# axiom_beta_sensor_cmv12000_v0_14_tht_73a.net
KiCad netlist of a schematic drawn in EAGLE
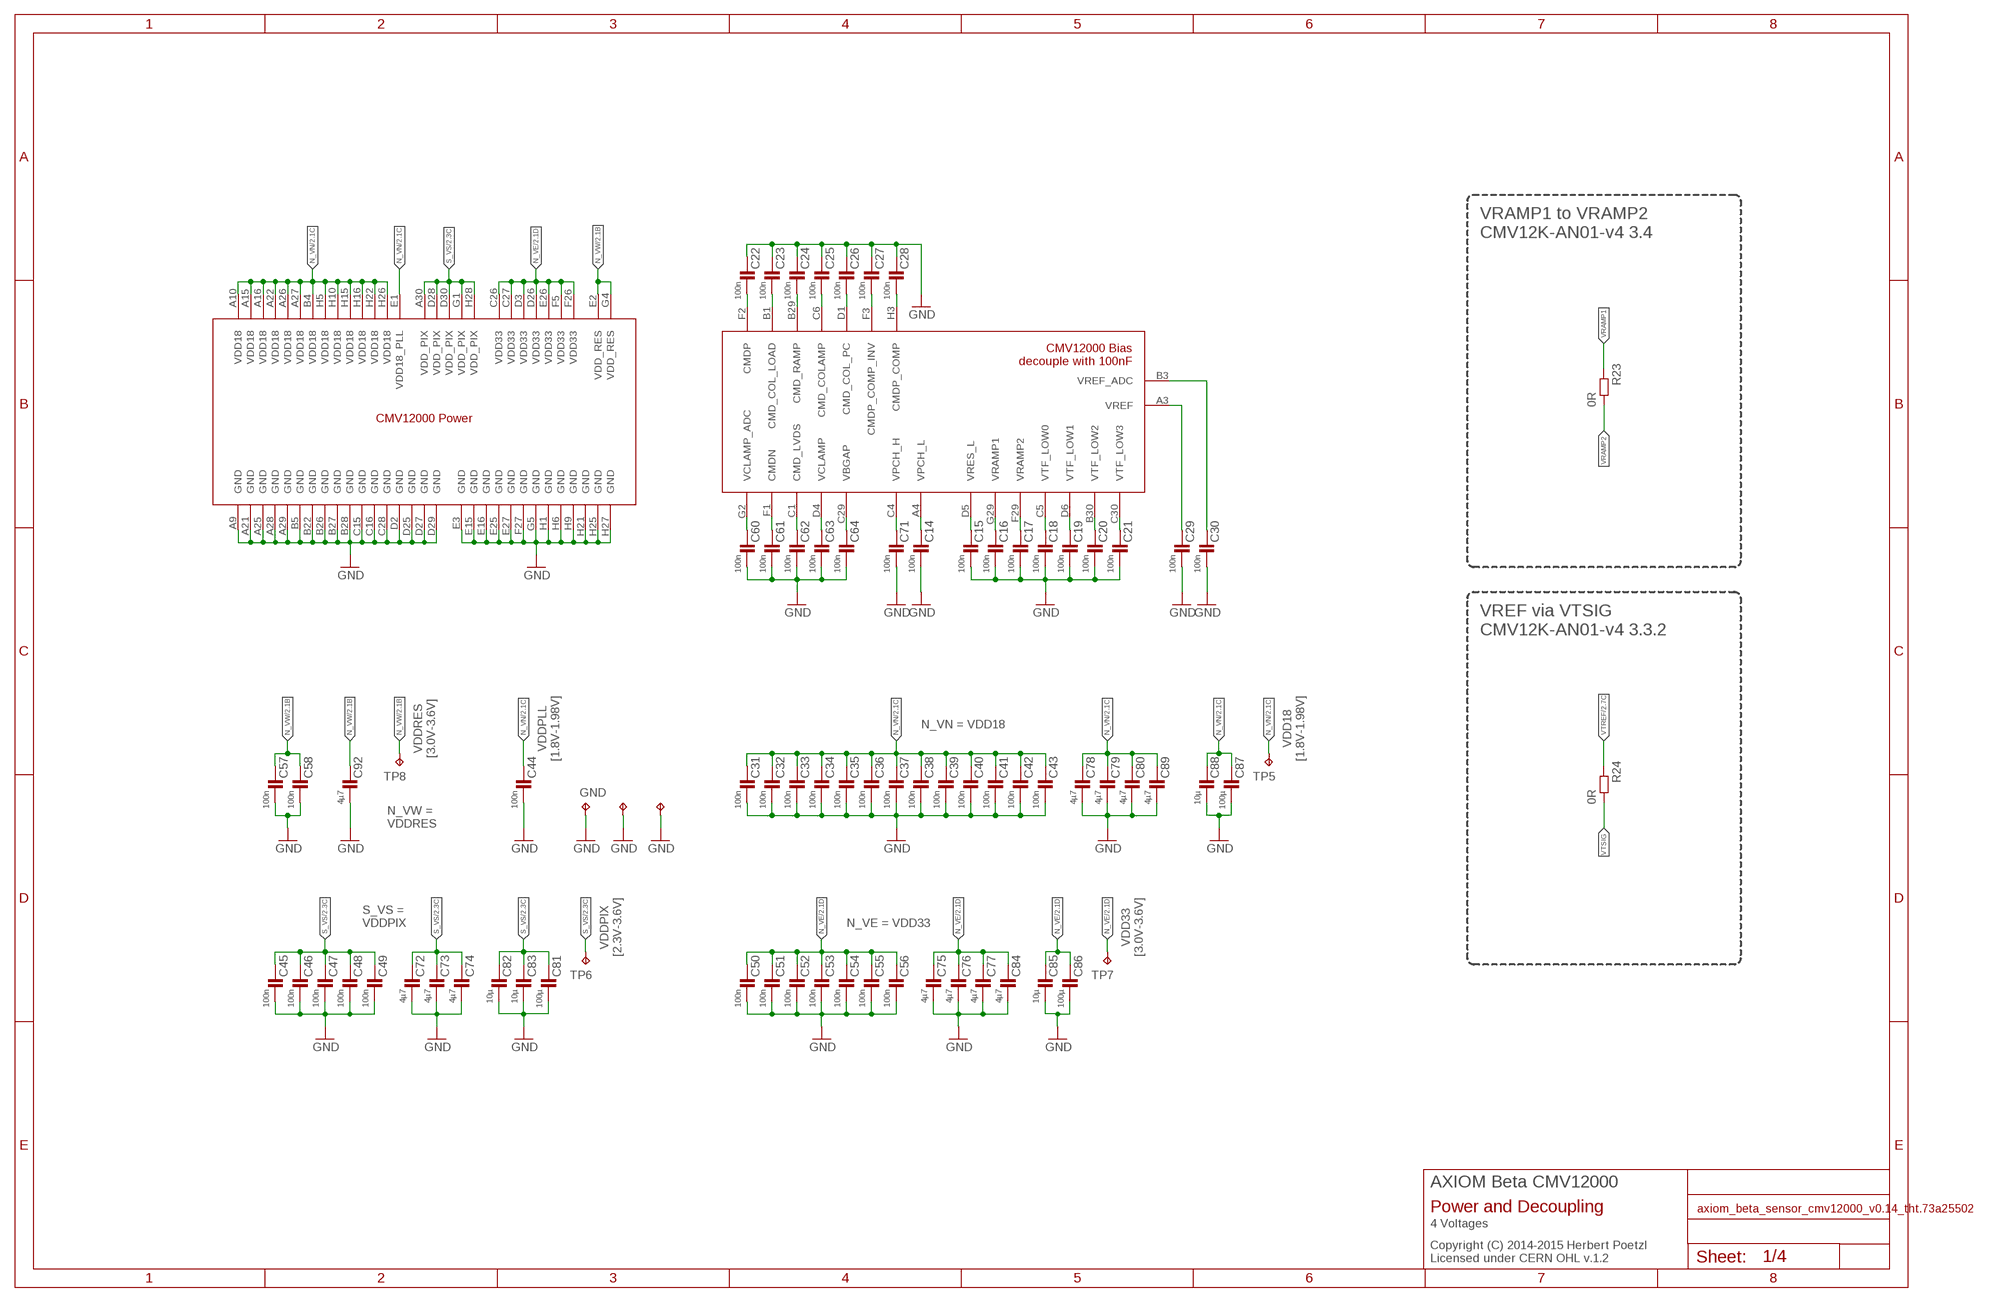
[diagram p0: schematic, sheet 1]
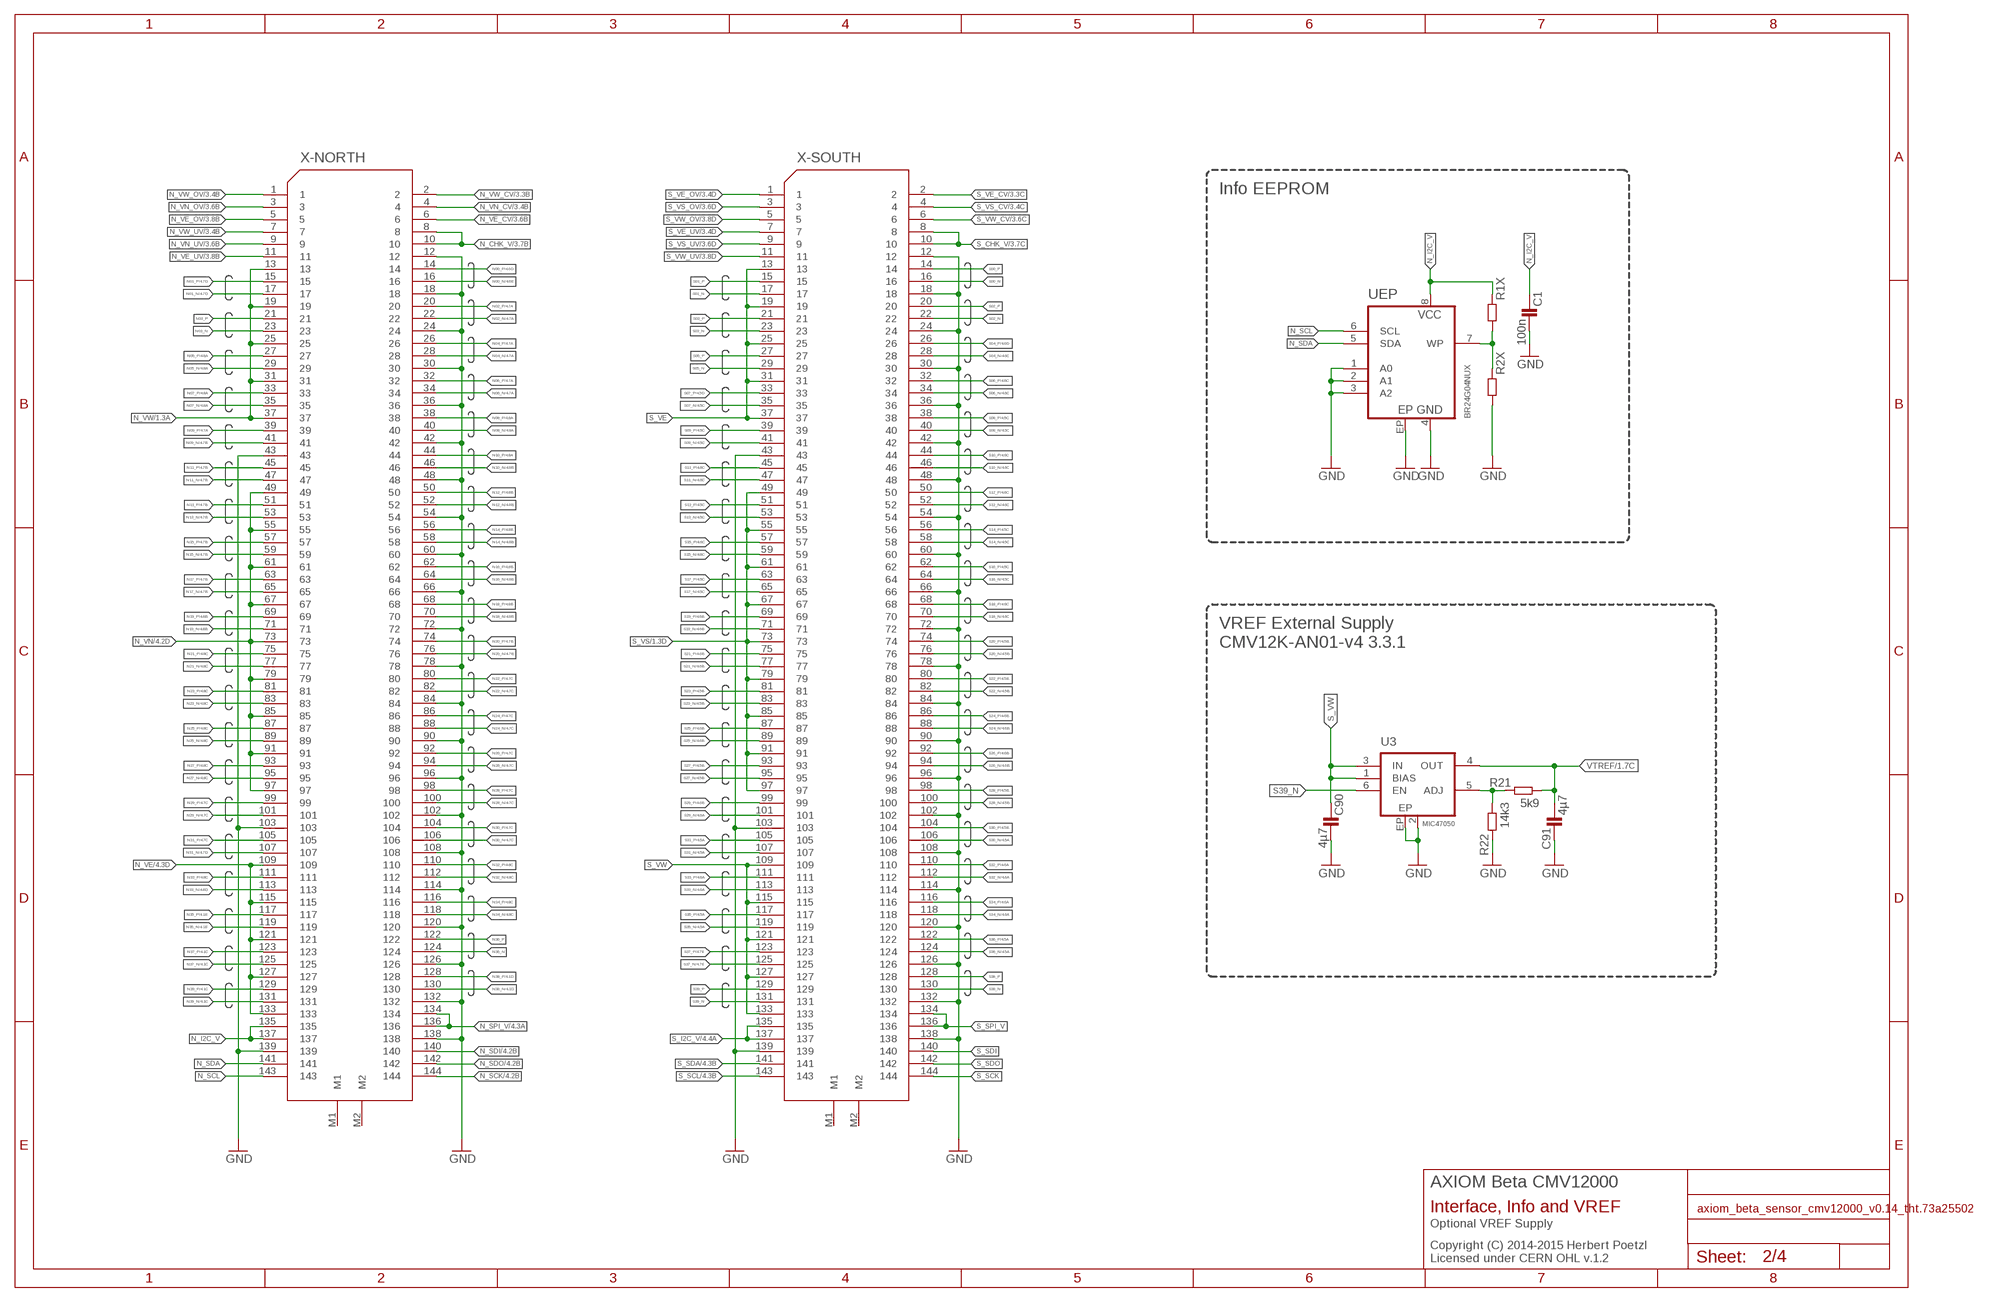
[diagram p1: schematic, sheet 2]
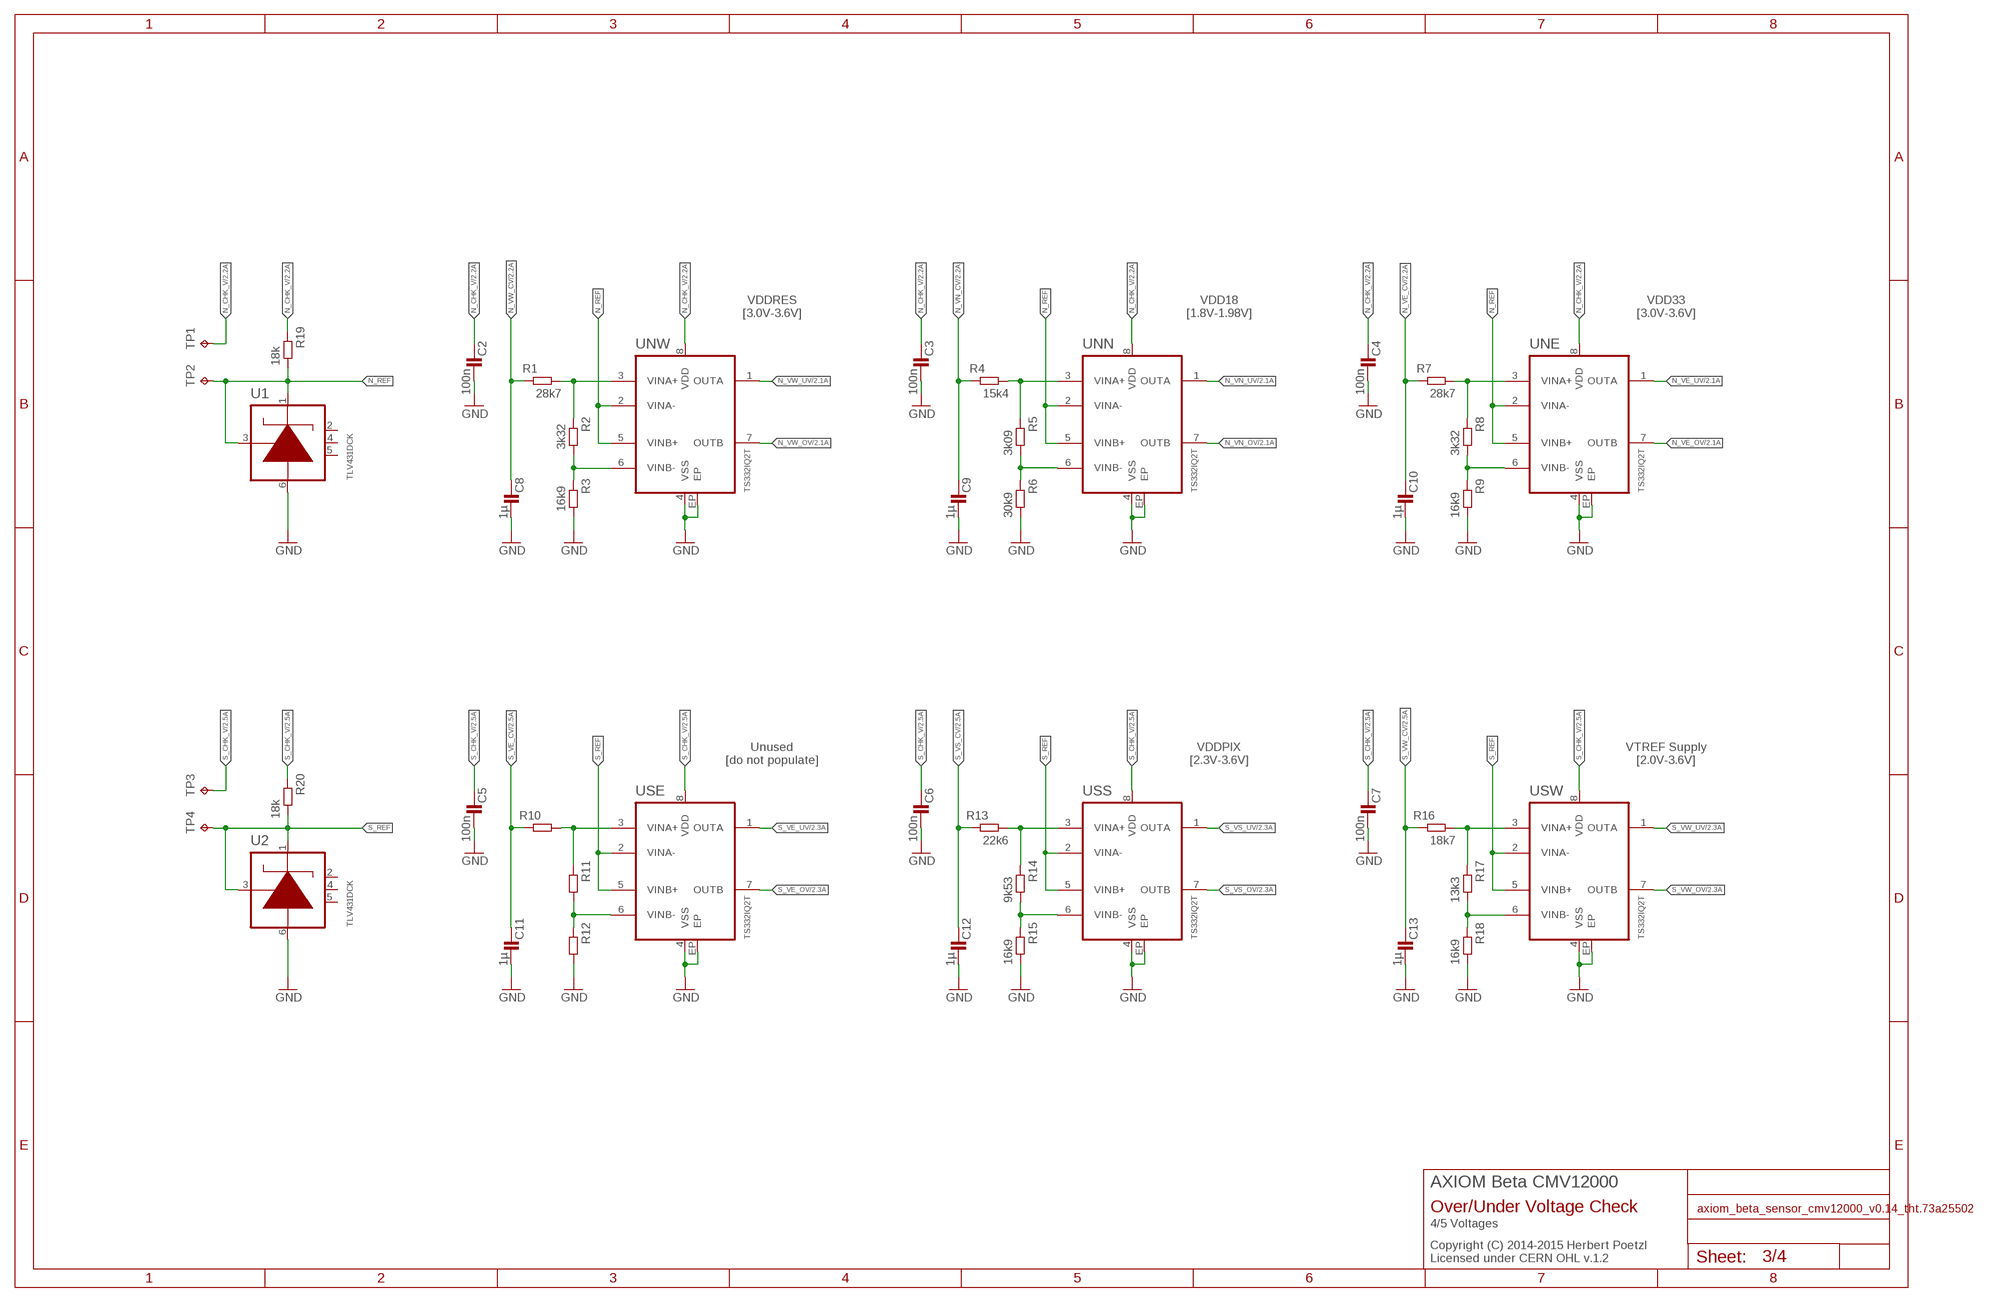
[diagram p2: schematic, sheet 3]
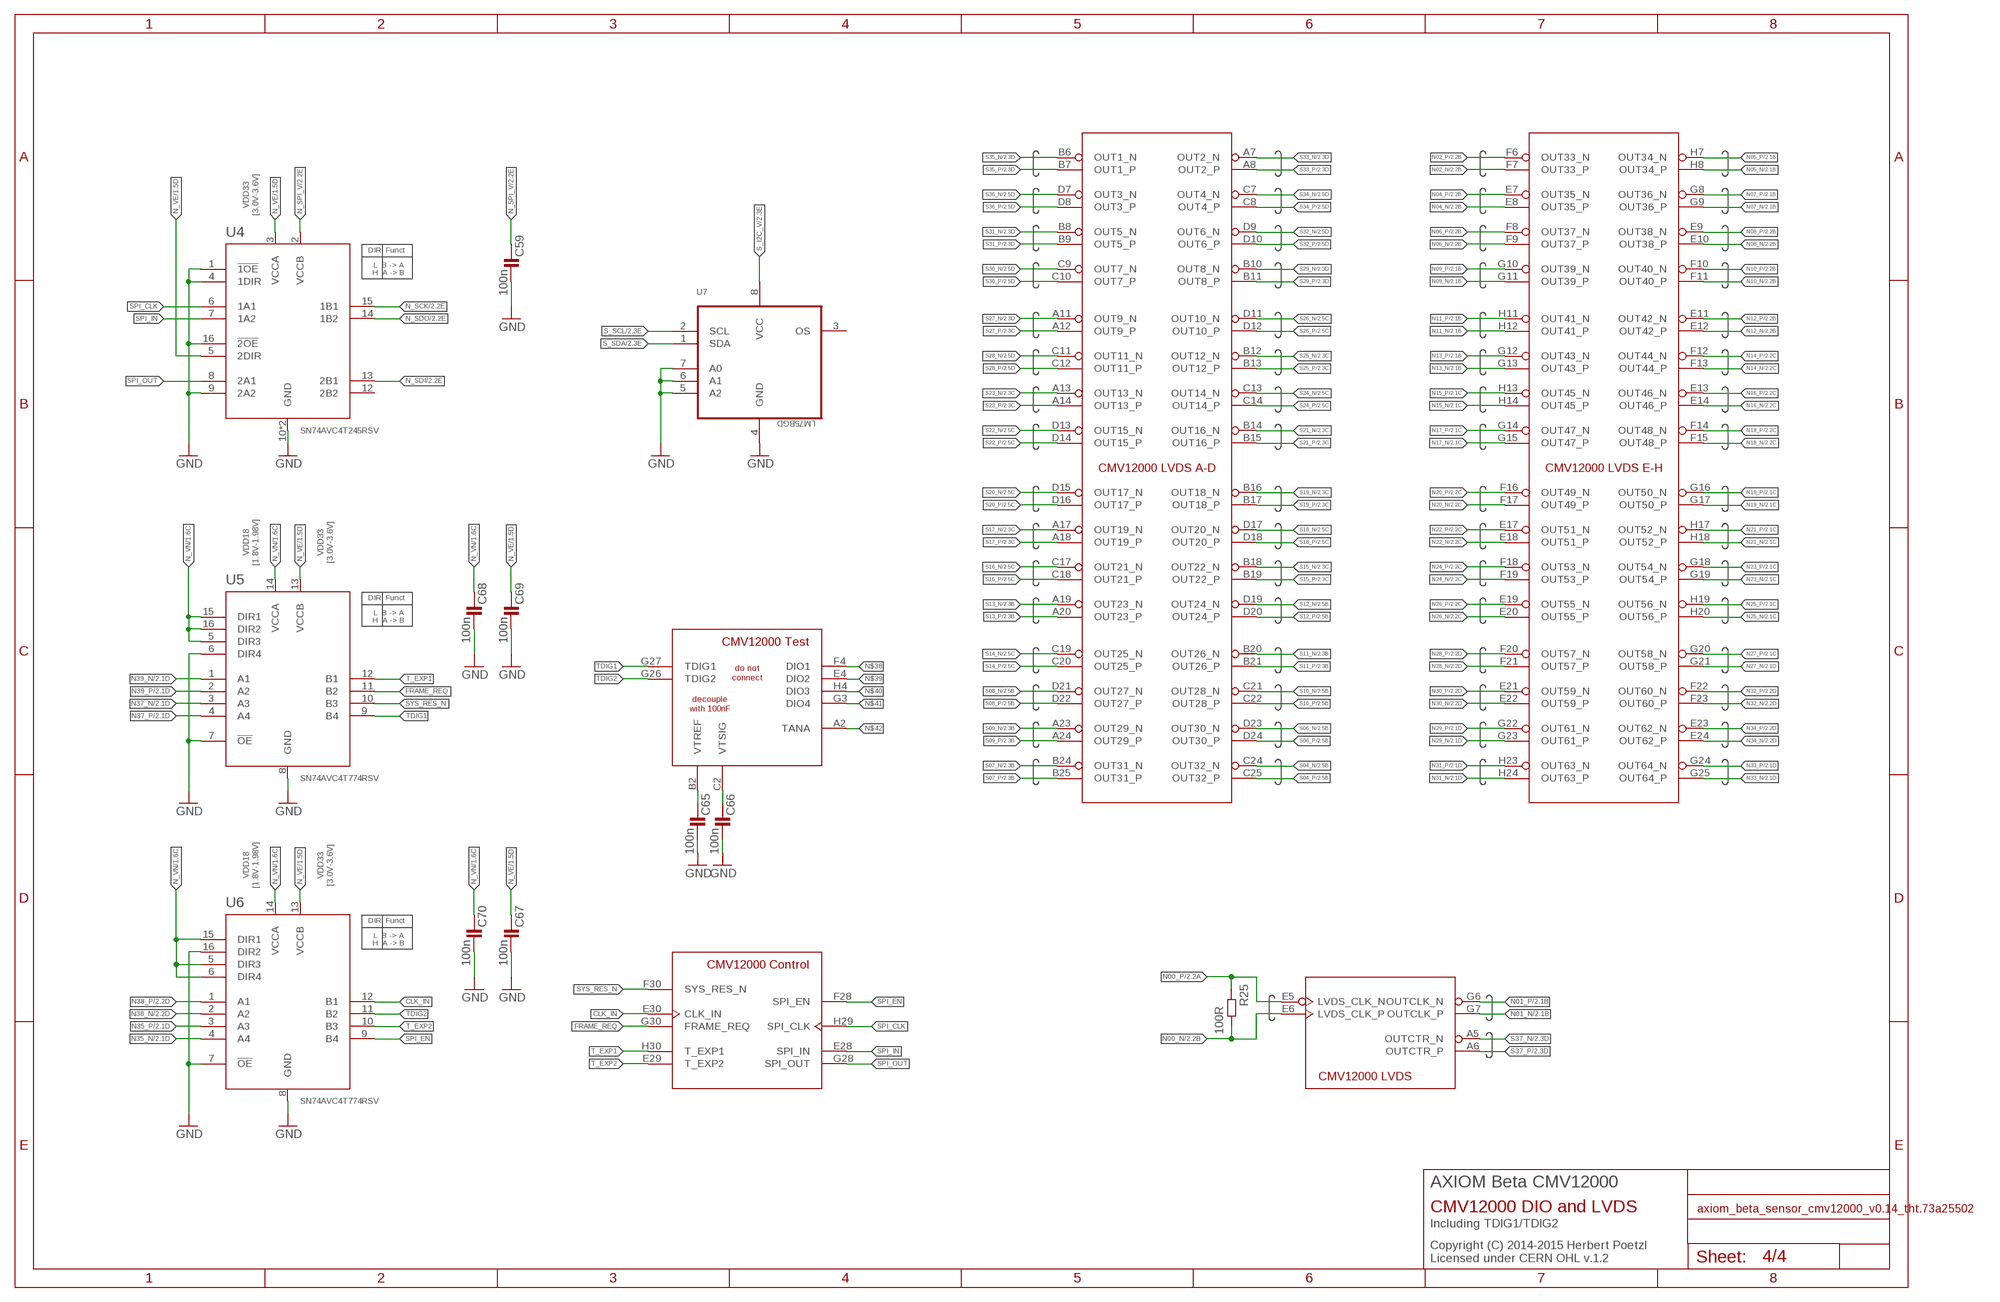
[diagram p3: schematic, sheet 4]

(export (version "E")
  (design (tool "Eeschema 10.0.6"))
  (components
    (comp (ref "C1")
      (value "100n")
      (footprint "eagle-import:0402-C")
      (libsource (lib "eagle-import") (part "C0402-C"))
    )
    (comp (ref "C90")
      (value "4µ7")
      (footprint "eagle-import:0402-C")
      (libsource (lib "eagle-import") (part "C0402-C"))
    )
    (comp (ref "C91")
      (value "4µ7")
      (footprint "eagle-import:0402-C")
      (libsource (lib "eagle-import") (part "C0402-C"))
    )
    (comp (ref "R1X")
      (value "R0402-C")
      (footprint "eagle-import:0402-C")
      (libsource (lib "eagle-import") (part "R0402-C"))
    )
    (comp (ref "R2X")
      (value "R0402-C")
      (footprint "eagle-import:0402-C")
      (libsource (lib "eagle-import") (part "R0402-C"))
    )
    (comp (ref "R21")
      (value "5k9")
      (footprint "eagle-import:0402-C")
      (libsource (lib "eagle-import") (part "R0402-C"))
    )
    (comp (ref "R22")
      (value "14k3")
      (footprint "eagle-import:0402-C")
      (libsource (lib "eagle-import") (part "R0402-C"))
    )
    (comp (ref "U3")
      (value "MIC47050")
      (footprint "eagle-import:MLF-6")
      (libsource (lib "eagle-import") (part "MIC47050-ADJ"))
    )
    (comp (ref "UEP")
      (value "BR24G04NUX")
      (footprint "eagle-import:DFN200X300X100-9N")
      (libsource (lib "eagle-import") (part "BR24G04NUX"))
    )
    (comp (ref "X-NORTH")
      (value "FX10-144P")
      (footprint "eagle-import:FX10A-144P")
      (libsource (lib "eagle-import") (part "FX10-144P"))
    )
    (comp (ref "X-SOUTH")
      (value "FX10-144P")
      (footprint "eagle-import:FX10A-144P")
      (libsource (lib "eagle-import") (part "FX10-144P"))
    )
    (comp (ref "C2")
      (value "100n")
      (footprint "eagle-import:0402-C")
      (libsource (lib "eagle-import") (part "C0402-C"))
    )
    (comp (ref "C3")
      (value "100n")
      (footprint "eagle-import:0402-C")
      (libsource (lib "eagle-import") (part "C0402-C"))
    )
    (comp (ref "C4")
      (value "100n")
      (footprint "eagle-import:0402-C")
      (libsource (lib "eagle-import") (part "C0402-C"))
    )
    (comp (ref "C5")
      (value "100n")
      (footprint "eagle-import:0402-C")
      (libsource (lib "eagle-import") (part "C0402-C"))
    )
    (comp (ref "C6")
      (value "100n")
      (footprint "eagle-import:0402-C")
      (libsource (lib "eagle-import") (part "C0402-C"))
    )
    (comp (ref "C7")
      (value "100n")
      (footprint "eagle-import:0402-C")
      (libsource (lib "eagle-import") (part "C0402-C"))
    )
    (comp (ref "C8")
      (value "1µ")
      (footprint "eagle-import:0402-C")
      (libsource (lib "eagle-import") (part "C0402-C"))
    )
    (comp (ref "C9")
      (value "1µ")
      (footprint "eagle-import:0402-C")
      (libsource (lib "eagle-import") (part "C0402-C"))
    )
    (comp (ref "C10")
      (value "1µ")
      (footprint "eagle-import:0402-C")
      (libsource (lib "eagle-import") (part "C0402-C"))
    )
    (comp (ref "C11")
      (value "1µ")
      (footprint "eagle-import:0402-C")
      (libsource (lib "eagle-import") (part "C0402-C"))
    )
    (comp (ref "C12")
      (value "1µ")
      (footprint "eagle-import:0402-C")
      (libsource (lib "eagle-import") (part "C0402-C"))
    )
    (comp (ref "C13")
      (value "1µ")
      (footprint "eagle-import:0402-C")
      (libsource (lib "eagle-import") (part "C0402-C"))
    )
    (comp (ref "R1")
      (value "28k7")
      (footprint "eagle-import:0402-C")
      (libsource (lib "eagle-import") (part "R0402-C"))
    )
    (comp (ref "R2")
      (value "3k32")
      (footprint "eagle-import:0402-C")
      (libsource (lib "eagle-import") (part "R0402-C"))
    )
    (comp (ref "R3")
      (value "16k9")
      (footprint "eagle-import:0402-C")
      (libsource (lib "eagle-import") (part "R0402-C"))
    )
    (comp (ref "R4")
      (value "15k4")
      (footprint "eagle-import:0402-C")
      (libsource (lib "eagle-import") (part "R0402-C"))
    )
    (comp (ref "R5")
      (value "3k09")
      (footprint "eagle-import:0402-C")
      (libsource (lib "eagle-import") (part "R0402-C"))
    )
    (comp (ref "R6")
      (value "30k9")
      (footprint "eagle-import:0402-C")
      (libsource (lib "eagle-import") (part "R0402-C"))
    )
    (comp (ref "R7")
      (value "28k7")
      (footprint "eagle-import:0402-C")
      (libsource (lib "eagle-import") (part "R0402-C"))
    )
    (comp (ref "R8")
      (value "3k32")
      (footprint "eagle-import:0402-C")
      (libsource (lib "eagle-import") (part "R0402-C"))
    )
    (comp (ref "R9")
      (value "16k9")
      (footprint "eagle-import:0402-C")
      (libsource (lib "eagle-import") (part "R0402-C"))
    )
    (comp (ref "R10")
      (value "R0402-C")
      (footprint "eagle-import:0402-C")
      (libsource (lib "eagle-import") (part "R0402-C"))
    )
    (comp (ref "R11")
      (value "R0402-C")
      (footprint "eagle-import:0402-C")
      (libsource (lib "eagle-import") (part "R0402-C"))
    )
    (comp (ref "R12")
      (value "R0402-C")
      (footprint "eagle-import:0402-C")
      (libsource (lib "eagle-import") (part "R0402-C"))
    )
    (comp (ref "R13")
      (value "22k6")
      (footprint "eagle-import:0402-C")
      (libsource (lib "eagle-import") (part "R0402-C"))
    )
    (comp (ref "R14")
      (value "9k53")
      (footprint "eagle-import:0402-C")
      (libsource (lib "eagle-import") (part "R0402-C"))
    )
    (comp (ref "R15")
      (value "16k9")
      (footprint "eagle-import:0402-C")
      (libsource (lib "eagle-import") (part "R0402-C"))
    )
    (comp (ref "R16")
      (value "18k7")
      (footprint "eagle-import:0402-C")
      (libsource (lib "eagle-import") (part "R0402-C"))
    )
    (comp (ref "R17")
      (value "13k3")
      (footprint "eagle-import:0402-C")
      (libsource (lib "eagle-import") (part "R0402-C"))
    )
    (comp (ref "R18")
      (value "16k9")
      (footprint "eagle-import:0402-C")
      (libsource (lib "eagle-import") (part "R0402-C"))
    )
    (comp (ref "R19")
      (value "18k")
      (footprint "eagle-import:0402-C")
      (libsource (lib "eagle-import") (part "R0402-C"))
    )
    (comp (ref "R20")
      (value "18k")
      (footprint "eagle-import:0402-C")
      (libsource (lib "eagle-import") (part "R0402-C"))
    )
    (comp (ref "TP1")
      (value "TPTP10R")
      (footprint "eagle-import:TP10R")
      (libsource (lib "eagle-import") (part "TPTP10R"))
    )
    (comp (ref "TP2")
      (value "TPTP10R")
      (footprint "eagle-import:TP10R")
      (libsource (lib "eagle-import") (part "TPTP10R"))
    )
    (comp (ref "TP3")
      (value "TPTP10R")
      (footprint "eagle-import:TP10R")
      (libsource (lib "eagle-import") (part "TPTP10R"))
    )
    (comp (ref "TP4")
      (value "TPTP10R")
      (footprint "eagle-import:TP10R")
      (libsource (lib "eagle-import") (part "TPTP10R"))
    )
    (comp (ref "U1")
      (value "TLV431DCK")
      (footprint "eagle-import:SOT65P210X110-6N")
      (libsource (lib "eagle-import") (part "TLV431DCK"))
    )
    (comp (ref "U2")
      (value "TLV431DCK")
      (footprint "eagle-import:SOT65P210X110-6N")
      (libsource (lib "eagle-import") (part "TLV431DCK"))
    )
    (comp (ref "UNE")
      (value "TS332IQ2T")
      (footprint "eagle-import:DFN200X200X100-9N")
      (libsource (lib "eagle-import") (part "TS332IQ2T"))
    )
    (comp (ref "UNN")
      (value "TS332IQ2T")
      (footprint "eagle-import:DFN200X200X100-9N")
      (libsource (lib "eagle-import") (part "TS332IQ2T"))
    )
    (comp (ref "UNW")
      (value "TS332IQ2T")
      (footprint "eagle-import:DFN200X200X100-9N")
      (libsource (lib "eagle-import") (part "TS332IQ2T"))
    )
    (comp (ref "USE")
      (value "TS332IQ2T")
      (footprint "eagle-import:DFN200X200X100-9N")
      (libsource (lib "eagle-import") (part "TS332IQ2T"))
    )
    (comp (ref "USS")
      (value "TS332IQ2T")
      (footprint "eagle-import:DFN200X200X100-9N")
      (libsource (lib "eagle-import") (part "TS332IQ2T"))
    )
    (comp (ref "USW")
      (value "TS332IQ2T")
      (footprint "eagle-import:DFN200X200X100-9N")
      (libsource (lib "eagle-import") (part "TS332IQ2T"))
    )
    (comp (ref "C14")
      (value "100n")
      (footprint "eagle-import:0402-C")
      (libsource (lib "eagle-import") (part "C0402-C"))
    )
    (comp (ref "C15")
      (value "100n")
      (footprint "eagle-import:0402-C")
      (libsource (lib "eagle-import") (part "C0402-C"))
    )
    (comp (ref "C16")
      (value "100n")
      (footprint "eagle-import:0402-C")
      (libsource (lib "eagle-import") (part "C0402-C"))
    )
    (comp (ref "C17")
      (value "100n")
      (footprint "eagle-import:0402-C")
      (libsource (lib "eagle-import") (part "C0402-C"))
    )
    (comp (ref "C18")
      (value "100n")
      (footprint "eagle-import:0402-C")
      (libsource (lib "eagle-import") (part "C0402-C"))
    )
    (comp (ref "C19")
      (value "100n")
      (footprint "eagle-import:0402-C")
      (libsource (lib "eagle-import") (part "C0402-C"))
    )
    (comp (ref "C20")
      (value "100n")
      (footprint "eagle-import:0402-C")
      (libsource (lib "eagle-import") (part "C0402-C"))
    )
    (comp (ref "C21")
      (value "100n")
      (footprint "eagle-import:0402-C")
      (libsource (lib "eagle-import") (part "C0402-C"))
    )
    (comp (ref "C22")
      (value "100n")
      (footprint "eagle-import:0402-C")
      (libsource (lib "eagle-import") (part "C0402-C"))
    )
    (comp (ref "C23")
      (value "100n")
      (footprint "eagle-import:0402-C")
      (libsource (lib "eagle-import") (part "C0402-C"))
    )
    (comp (ref "C24")
      (value "100n")
      (footprint "eagle-import:0402-C")
      (libsource (lib "eagle-import") (part "C0402-C"))
    )
    (comp (ref "C25")
      (value "100n")
      (footprint "eagle-import:0402-C")
      (libsource (lib "eagle-import") (part "C0402-C"))
    )
    (comp (ref "C26")
      (value "100n")
      (footprint "eagle-import:0402-C")
      (libsource (lib "eagle-import") (part "C0402-C"))
    )
    (comp (ref "C27")
      (value "100n")
      (footprint "eagle-import:0402-C")
      (libsource (lib "eagle-import") (part "C0402-C"))
    )
    (comp (ref "C28")
      (value "100n")
      (footprint "eagle-import:0402-C")
      (libsource (lib "eagle-import") (part "C0402-C"))
    )
    (comp (ref "C29")
      (value "100n")
      (footprint "eagle-import:0402-C")
      (libsource (lib "eagle-import") (part "C0402-C"))
    )
    (comp (ref "C30")
      (value "100n")
      (footprint "eagle-import:0402-C")
      (libsource (lib "eagle-import") (part "C0402-C"))
    )
    (comp (ref "C31")
      (value "100n")
      (footprint "eagle-import:0402-C")
      (libsource (lib "eagle-import") (part "C0402-C"))
    )
    (comp (ref "C32")
      (value "100n")
      (footprint "eagle-import:0402-C")
      (libsource (lib "eagle-import") (part "C0402-C"))
    )
    (comp (ref "C33")
      (value "100n")
      (footprint "eagle-import:0402-C")
      (libsource (lib "eagle-import") (part "C0402-C"))
    )
    (comp (ref "C34")
      (value "100n")
      (footprint "eagle-import:0402-C")
      (libsource (lib "eagle-import") (part "C0402-C"))
    )
    (comp (ref "C35")
      (value "100n")
      (footprint "eagle-import:0402-C")
      (libsource (lib "eagle-import") (part "C0402-C"))
    )
    (comp (ref "C36")
      (value "100n")
      (footprint "eagle-import:0402-C")
      (libsource (lib "eagle-import") (part "C0402-C"))
    )
    (comp (ref "C37")
      (value "100n")
      (footprint "eagle-import:0402-C")
      (libsource (lib "eagle-import") (part "C0402-C"))
    )
    (comp (ref "C38")
      (value "100n")
      (footprint "eagle-import:0402-C")
      (libsource (lib "eagle-import") (part "C0402-C"))
    )
    (comp (ref "C39")
      (value "100n")
      (footprint "eagle-import:0402-C")
      (libsource (lib "eagle-import") (part "C0402-C"))
    )
    (comp (ref "C40")
      (value "100n")
      (footprint "eagle-import:0402-C")
      (libsource (lib "eagle-import") (part "C0402-C"))
    )
    (comp (ref "C41")
      (value "100n")
      (footprint "eagle-import:0402-C")
      (libsource (lib "eagle-import") (part "C0402-C"))
    )
    (comp (ref "C42")
      (value "100n")
      (footprint "eagle-import:0402-C")
      (libsource (lib "eagle-import") (part "C0402-C"))
    )
    (comp (ref "C43")
      (value "100n")
      (footprint "eagle-import:0402-C")
      (libsource (lib "eagle-import") (part "C0402-C"))
    )
    (comp (ref "C44")
      (value "100n")
      (footprint "eagle-import:0402-C")
      (libsource (lib "eagle-import") (part "C0402-C"))
    )
    (comp (ref "C45")
      (value "100n")
      (footprint "eagle-import:0402-C")
      (libsource (lib "eagle-import") (part "C0402-C"))
    )
    (comp (ref "C46")
      (value "100n")
      (footprint "eagle-import:0402-C")
      (libsource (lib "eagle-import") (part "C0402-C"))
    )
    (comp (ref "C47")
      (value "100n")
      (footprint "eagle-import:0402-C")
      (libsource (lib "eagle-import") (part "C0402-C"))
    )
    (comp (ref "C48")
      (value "100n")
      (footprint "eagle-import:0402-C")
      (libsource (lib "eagle-import") (part "C0402-C"))
    )
    (comp (ref "C49")
      (value "100n")
      (footprint "eagle-import:0402-C")
      (libsource (lib "eagle-import") (part "C0402-C"))
    )
    (comp (ref "C50")
      (value "100n")
      (footprint "eagle-import:0402-C")
      (libsource (lib "eagle-import") (part "C0402-C"))
    )
    (comp (ref "C51")
      (value "100n")
      (footprint "eagle-import:0402-C")
      (libsource (lib "eagle-import") (part "C0402-C"))
    )
    (comp (ref "C52")
      (value "100n")
      (footprint "eagle-import:0402-C")
      (libsource (lib "eagle-import") (part "C0402-C"))
    )
    (comp (ref "C53")
      (value "100n")
      (footprint "eagle-import:0402-C")
      (libsource (lib "eagle-import") (part "C0402-C"))
    )
    (comp (ref "C54")
      (value "100n")
      (footprint "eagle-import:0402-C")
      (libsource (lib "eagle-import") (part "C0402-C"))
    )
    (comp (ref "C55")
      (value "100n")
      (footprint "eagle-import:0402-C")
      (libsource (lib "eagle-import") (part "C0402-C"))
    )
    (comp (ref "C56")
      (value "100n")
      (footprint "eagle-import:0402-C")
      (libsource (lib "eagle-import") (part "C0402-C"))
    )
    (comp (ref "C57")
      (value "100n")
      (footprint "eagle-import:0402-C")
      (libsource (lib "eagle-import") (part "C0402-C"))
    )
    (comp (ref "C58")
      (value "100n")
      (footprint "eagle-import:0402-C")
      (libsource (lib "eagle-import") (part "C0402-C"))
    )
    (comp (ref "C60")
      (value "100n")
      (footprint "eagle-import:0402-C")
      (libsource (lib "eagle-import") (part "C0402-C"))
    )
    (comp (ref "C61")
      (value "100n")
      (footprint "eagle-import:0402-C")
      (libsource (lib "eagle-import") (part "C0402-C"))
    )
    (comp (ref "C62")
      (value "100n")
      (footprint "eagle-import:0402-C")
      (libsource (lib "eagle-import") (part "C0402-C"))
    )
    (comp (ref "C63")
      (value "100n")
      (footprint "eagle-import:0402-C")
      (libsource (lib "eagle-import") (part "C0402-C"))
    )
    (comp (ref "C64")
      (value "100n")
      (footprint "eagle-import:0402-C")
      (libsource (lib "eagle-import") (part "C0402-C"))
    )
    (comp (ref "C71")
      (value "100n")
      (footprint "eagle-import:0402-C")
      (libsource (lib "eagle-import") (part "C0402-C"))
    )
    (comp (ref "C72")
      (value "4µ7")
      (footprint "eagle-import:0402-B")
      (libsource (lib "eagle-import") (part "C0402-B"))
    )
    (comp (ref "C73")
      (value "4µ7")
      (footprint "eagle-import:0402-C")
      (libsource (lib "eagle-import") (part "C0402-C"))
    )
    (comp (ref "C74")
      (value "4µ7")
      (footprint "eagle-import:0402-C")
      (libsource (lib "eagle-import") (part "C0402-C"))
    )
    (comp (ref "C75")
      (value "4µ7")
      (footprint "eagle-import:0402-C")
      (libsource (lib "eagle-import") (part "C0402-C"))
    )
    (comp (ref "C76")
      (value "4µ7")
      (footprint "eagle-import:0402-C")
      (libsource (lib "eagle-import") (part "C0402-C"))
    )
    (comp (ref "C77")
      (value "4µ7")
      (footprint "eagle-import:0402-B")
      (libsource (lib "eagle-import") (part "C0402-B"))
    )
    (comp (ref "C78")
      (value "4µ7")
      (footprint "eagle-import:0402-B")
      (libsource (lib "eagle-import") (part "C0402-B"))
    )
    (comp (ref "C79")
      (value "4µ7")
      (footprint "eagle-import:0402-C")
      (libsource (lib "eagle-import") (part "C0402-C"))
    )
    (comp (ref "C80")
      (value "4µ7")
      (footprint "eagle-import:0402-C")
      (libsource (lib "eagle-import") (part "C0402-C"))
    )
    (comp (ref "C81")
      (value "100µ")
      (footprint "eagle-import:1206-B")
      (libsource (lib "eagle-import") (part "C1206-B"))
    )
    (comp (ref "C82")
      (value "10µ")
      (footprint "eagle-import:0603-C")
      (libsource (lib "eagle-import") (part "C0603-C"))
    )
    (comp (ref "C83")
      (value "10µ")
      (footprint "eagle-import:0603-C")
      (libsource (lib "eagle-import") (part "C0603-C"))
    )
    (comp (ref "C84")
      (value "4µ7")
      (footprint "eagle-import:0402-C")
      (libsource (lib "eagle-import") (part "C0402-C"))
    )
    (comp (ref "C85")
      (value "10µ")
      (footprint "eagle-import:0603-C")
      (libsource (lib "eagle-import") (part "C0603-C"))
    )
    (comp (ref "C86")
      (value "100µ")
      (footprint "eagle-import:1206-B")
      (libsource (lib "eagle-import") (part "C1206-B"))
    )
    (comp (ref "C87")
      (value "100µ")
      (footprint "eagle-import:1206-B")
      (libsource (lib "eagle-import") (part "C1206-B"))
    )
    (comp (ref "C88")
      (value "10µ")
      (footprint "eagle-import:0603-C")
      (libsource (lib "eagle-import") (part "C0603-C"))
    )
    (comp (ref "C89")
      (value "4µ7")
      (footprint "eagle-import:0402-C")
      (libsource (lib "eagle-import") (part "C0402-C"))
    )
    (comp (ref "C92")
      (value "4µ7")
      (footprint "eagle-import:0402-C")
      (libsource (lib "eagle-import") (part "C0402-C"))
    )
    (comp (ref "GND")
      (value "TPTP10R")
      (footprint "eagle-import:TP10R")
      (libsource (lib "eagle-import") (part "TPTP10R"))
    )
    (comp (ref "GND75")
      (value "TPTP10R")
      (footprint "eagle-import:TP10R")
      (libsource (lib "eagle-import") (part "TPTP10R"))
    )
    (comp (ref "GND77")
      (value "TPTP10R")
      (footprint "eagle-import:TP10R")
      (libsource (lib "eagle-import") (part "TPTP10R"))
    )
    (comp (ref "R23")
      (value "0R")
      (footprint "eagle-import:0402-C")
      (libsource (lib "eagle-import") (part "R0402-C"))
    )
    (comp (ref "R24")
      (value "0R")
      (footprint "eagle-import:0402-C")
      (libsource (lib "eagle-import") (part "R0402-C"))
    )
    (comp (ref "SENSOR")
      (value "CMV12000ANDON")
      (footprint "eagle-import:10-30-07-237-400T4")
      (libsource (lib "eagle-import") (part "CMV12000ANDON"))
    )
    (comp (ref "TP5")
      (value "TPTP10R")
      (footprint "eagle-import:TP10R")
      (libsource (lib "eagle-import") (part "TPTP10R"))
    )
    (comp (ref "TP6")
      (value "TPTP10R")
      (footprint "eagle-import:TP10R")
      (libsource (lib "eagle-import") (part "TPTP10R"))
    )
    (comp (ref "TP7")
      (value "TPTP10R")
      (footprint "eagle-import:TP10R")
      (libsource (lib "eagle-import") (part "TPTP10R"))
    )
    (comp (ref "TP8")
      (value "TPTP10R")
      (footprint "eagle-import:TP10R")
      (libsource (lib "eagle-import") (part "TPTP10R"))
    )
    (comp (ref "C59")
      (value "100n")
      (footprint "eagle-import:0402-C")
      (libsource (lib "eagle-import") (part "C0402-C"))
    )
    (comp (ref "C65")
      (value "100n")
      (footprint "eagle-import:0402-C")
      (libsource (lib "eagle-import") (part "C0402-C"))
    )
    (comp (ref "C66")
      (value "100n")
      (footprint "eagle-import:0402-C")
      (libsource (lib "eagle-import") (part "C0402-C"))
    )
    (comp (ref "C67")
      (value "100n")
      (footprint "eagle-import:0402-C")
      (libsource (lib "eagle-import") (part "C0402-C"))
    )
    (comp (ref "C68")
      (value "100n")
      (footprint "eagle-import:0402-C")
      (libsource (lib "eagle-import") (part "C0402-C"))
    )
    (comp (ref "C69")
      (value "100n")
      (footprint "eagle-import:0402-C")
      (libsource (lib "eagle-import") (part "C0402-C"))
    )
    (comp (ref "C70")
      (value "100n")
      (footprint "eagle-import:0402-C")
      (libsource (lib "eagle-import") (part "C0402-C"))
    )
    (comp (ref "R25")
      (value "100R")
      (footprint "eagle-import:0402-C")
      (libsource (lib "eagle-import") (part "R0402-C"))
    )
    (comp (ref "U4")
      (value "SN74AVC4T245RSV")
      (footprint "eagle-import:QFN40P185X265X55-16N")
      (libsource (lib "eagle-import") (part "SN74AVC4T245RSV"))
    )
    (comp (ref "U5")
      (value "SN74AVC4T774RSV")
      (footprint "eagle-import:QFN40P185X265X55-16N")
      (libsource (lib "eagle-import") (part "SN74AVC4T774RSV"))
    )
    (comp (ref "U6")
      (value "SN74AVC4T774RSV")
      (footprint "eagle-import:QFN40P185X265X55-16N")
      (libsource (lib "eagle-import") (part "SN74AVC4T774RSV"))
    )
    (comp (ref "U7")
      (value "LM75BGD")
      (footprint "eagle-import:SOT996-2_3")
      (libsource (lib "eagle-import") (part "LM75BGD"))
    )
  )
  (nets
    (net (code "1") (name "CLK_IN") (class "Default")
      (node (ref "SENSOR") (pin "E30") (pinfunction "CLK_IN_E30") (pintype "input"))
      (node (ref "U6") (pin "12") (pinfunction "B1_12") (pintype "bidirectional"))
    )
    (net (code "2") (name "FRAME_REQ") (class "Default")
      (node (ref "SENSOR") (pin "G30") (pinfunction "FRAME_REQ_G30") (pintype "input"))
      (node (ref "U5") (pin "11") (pinfunction "B2_11") (pintype "bidirectional"))
    )
    (net (code "3") (name "GND") (class "Default")
      (node (ref "C1") (pin "2") (pinfunction "2_2") (pintype "passive"))
      (node (ref "C10") (pin "2") (pinfunction "2_2") (pintype "passive"))
      (node (ref "C11") (pin "2") (pinfunction "2_2") (pintype "passive"))
      (node (ref "C12") (pin "2") (pinfunction "2_2") (pintype "passive"))
      (node (ref "C13") (pin "2") (pinfunction "2_2") (pintype "passive"))
      (node (ref "C14") (pin "2") (pinfunction "2_2") (pintype "passive"))
      (node (ref "C15") (pin "2") (pinfunction "2_2") (pintype "passive"))
      (node (ref "C16") (pin "2") (pinfunction "2_2") (pintype "passive"))
      (node (ref "C17") (pin "2") (pinfunction "2_2") (pintype "passive"))
      (node (ref "C18") (pin "2") (pinfunction "2_2") (pintype "passive"))
      (node (ref "C19") (pin "2") (pinfunction "2_2") (pintype "passive"))
      (node (ref "C2") (pin "2") (pinfunction "2_2") (pintype "passive"))
      (node (ref "C20") (pin "2") (pinfunction "2_2") (pintype "passive"))
      (node (ref "C21") (pin "2") (pinfunction "2_2") (pintype "passive"))
      (node (ref "C22") (pin "1") (pinfunction "1_1") (pintype "passive"))
      (node (ref "C23") (pin "1") (pinfunction "1_1") (pintype "passive"))
      (node (ref "C24") (pin "1") (pinfunction "1_1") (pintype "passive"))
      (node (ref "C25") (pin "1") (pinfunction "1_1") (pintype "passive"))
      (node (ref "C26") (pin "1") (pinfunction "1_1") (pintype "passive"))
      (node (ref "C27") (pin "1") (pinfunction "1_1") (pintype "passive"))
      (node (ref "C28") (pin "1") (pinfunction "1_1") (pintype "passive"))
      (node (ref "C29") (pin "2") (pinfunction "2_2") (pintype "passive"))
      (node (ref "C3") (pin "2") (pinfunction "2_2") (pintype "passive"))
      (node (ref "C30") (pin "2") (pinfunction "2_2") (pintype "passive"))
      (node (ref "C31") (pin "2") (pinfunction "2_2") (pintype "passive"))
      (node (ref "C32") (pin "2") (pinfunction "2_2") (pintype "passive"))
      (node (ref "C33") (pin "2") (pinfunction "2_2") (pintype "passive"))
      (node (ref "C34") (pin "2") (pinfunction "2_2") (pintype "passive"))
      (node (ref "C35") (pin "2") (pinfunction "2_2") (pintype "passive"))
      (node (ref "C36") (pin "2") (pinfunction "2_2") (pintype "passive"))
      (node (ref "C37") (pin "2") (pinfunction "2_2") (pintype "passive"))
      (node (ref "C38") (pin "2") (pinfunction "2_2") (pintype "passive"))
      (node (ref "C39") (pin "2") (pinfunction "2_2") (pintype "passive"))
      (node (ref "C4") (pin "2") (pinfunction "2_2") (pintype "passive"))
      (node (ref "C40") (pin "2") (pinfunction "2_2") (pintype "passive"))
      (node (ref "C41") (pin "2") (pinfunction "2_2") (pintype "passive"))
      (node (ref "C42") (pin "2") (pinfunction "2_2") (pintype "passive"))
      (node (ref "C43") (pin "2") (pinfunction "2_2") (pintype "passive"))
      (node (ref "C44") (pin "2") (pinfunction "2_2") (pintype "passive"))
      (node (ref "C45") (pin "2") (pinfunction "2_2") (pintype "passive"))
      (node (ref "C46") (pin "2") (pinfunction "2_2") (pintype "passive"))
      (node (ref "C47") (pin "2") (pinfunction "2_2") (pintype "passive"))
      (node (ref "C48") (pin "2") (pinfunction "2_2") (pintype "passive"))
      (node (ref "C49") (pin "2") (pinfunction "2_2") (pintype "passive"))
      (node (ref "C5") (pin "2") (pinfunction "2_2") (pintype "passive"))
      (node (ref "C50") (pin "2") (pinfunction "2_2") (pintype "passive"))
      (node (ref "C51") (pin "2") (pinfunction "2_2") (pintype "passive"))
      (node (ref "C52") (pin "2") (pinfunction "2_2") (pintype "passive"))
      (node (ref "C53") (pin "2") (pinfunction "2_2") (pintype "passive"))
      (node (ref "C54") (pin "2") (pinfunction "2_2") (pintype "passive"))
      (node (ref "C55") (pin "2") (pinfunction "2_2") (pintype "passive"))
      (node (ref "C56") (pin "2") (pinfunction "2_2") (pintype "passive"))
      (node (ref "C57") (pin "2") (pinfunction "2_2") (pintype "passive"))
      (node (ref "C58") (pin "2") (pinfunction "2_2") (pintype "passive"))
      (node (ref "C59") (pin "2") (pinfunction "2_2") (pintype "passive"))
      (node (ref "C6") (pin "2") (pinfunction "2_2") (pintype "passive"))
      (node (ref "C60") (pin "2") (pinfunction "2_2") (pintype "passive"))
      (node (ref "C61") (pin "2") (pinfunction "2_2") (pintype "passive"))
      (node (ref "C62") (pin "2") (pinfunction "2_2") (pintype "passive"))
      (node (ref "C63") (pin "2") (pinfunction "2_2") (pintype "passive"))
      (node (ref "C64") (pin "2") (pinfunction "2_2") (pintype "passive"))
      (node (ref "C65") (pin "2") (pinfunction "2_2") (pintype "passive"))
      (node (ref "C66") (pin "2") (pinfunction "2_2") (pintype "passive"))
      (node (ref "C67") (pin "2") (pinfunction "2_2") (pintype "passive"))
      (node (ref "C68") (pin "2") (pinfunction "2_2") (pintype "passive"))
      (node (ref "C69") (pin "2") (pinfunction "2_2") (pintype "passive"))
      (node (ref "C7") (pin "2") (pinfunction "2_2") (pintype "passive"))
      (node (ref "C70") (pin "2") (pinfunction "2_2") (pintype "passive"))
      (node (ref "C71") (pin "2") (pinfunction "2_2") (pintype "passive"))
      (node (ref "C72") (pin "2") (pinfunction "2_2") (pintype "passive"))
      (node (ref "C73") (pin "2") (pinfunction "2_2") (pintype "passive"))
      (node (ref "C74") (pin "2") (pinfunction "2_2") (pintype "passive"))
      (node (ref "C75") (pin "2") (pinfunction "2_2") (pintype "passive"))
      (node (ref "C76") (pin "2") (pinfunction "2_2") (pintype "passive"))
      (node (ref "C77") (pin "2") (pinfunction "2_2") (pintype "passive"))
      (node (ref "C78") (pin "2") (pinfunction "2_2") (pintype "passive"))
      (node (ref "C79") (pin "2") (pinfunction "2_2") (pintype "passive"))
      (node (ref "C8") (pin "2") (pinfunction "2_2") (pintype "passive"))
      (node (ref "C80") (pin "2") (pinfunction "2_2") (pintype "passive"))
      (node (ref "C81") (pin "2") (pinfunction "2_2") (pintype "passive"))
      (node (ref "C82") (pin "2") (pinfunction "2_2") (pintype "passive"))
      (node (ref "C83") (pin "2") (pinfunction "2_2") (pintype "passive"))
      (node (ref "C84") (pin "2") (pinfunction "2_2") (pintype "passive"))
      (node (ref "C85") (pin "2") (pinfunction "2_2") (pintype "passive"))
      (node (ref "C86") (pin "2") (pinfunction "2_2") (pintype "passive"))
      (node (ref "C87") (pin "2") (pinfunction "2_2") (pintype "passive"))
      (node (ref "C88") (pin "2") (pinfunction "2_2") (pintype "passive"))
      (node (ref "C89") (pin "2") (pinfunction "2_2") (pintype "passive"))
      (node (ref "C9") (pin "2") (pinfunction "2_2") (pintype "passive"))
      (node (ref "C90") (pin "2") (pinfunction "2_2") (pintype "passive"))
      (node (ref "C91") (pin "1") (pinfunction "1_1") (pintype "passive"))
      (node (ref "C92") (pin "2") (pinfunction "2_2") (pintype "passive"))
      (node (ref "GND") (pin "TP") (pinfunction "TP_TP") (pintype "input"))
      (node (ref "GND75") (pin "TP") (pinfunction "TP_TP") (pintype "input"))
      (node (ref "GND77") (pin "TP") (pinfunction "TP_TP") (pintype "input"))
      (node (ref "R12") (pin "2") (pinfunction "2_2") (pintype "passive"))
      (node (ref "R15") (pin "2") (pinfunction "2_2") (pintype "passive"))
      (node (ref "R18") (pin "2") (pinfunction "2_2") (pintype "passive"))
      (node (ref "R22") (pin "1") (pinfunction "1_1") (pintype "passive"))
      (node (ref "R2X") (pin "2") (pinfunction "2_2") (pintype "passive"))
      (node (ref "R3") (pin "2") (pinfunction "2_2") (pintype "passive"))
      (node (ref "R6") (pin "2") (pinfunction "2_2") (pintype "passive"))
      (node (ref "R9") (pin "2") (pinfunction "2_2") (pintype "passive"))
      (node (ref "SENSOR") (pin "A21") (pinfunction "GND_A21") (pintype "power_in"))
      (node (ref "SENSOR") (pin "A25") (pinfunction "GND_A25") (pintype "power_in"))
      (node (ref "SENSOR") (pin "A28") (pinfunction "GND_A28") (pintype "power_in"))
      (node (ref "SENSOR") (pin "A29") (pinfunction "GND_A29") (pintype "power_in"))
      (node (ref "SENSOR") (pin "A9") (pinfunction "GND_A9") (pintype "power_in"))
      (node (ref "SENSOR") (pin "B22") (pinfunction "GND_B22") (pintype "power_in"))
      (node (ref "SENSOR") (pin "B26") (pinfunction "GND_B26") (pintype "power_in"))
      (node (ref "SENSOR") (pin "B27") (pinfunction "GND_B27") (pintype "power_in"))
      (node (ref "SENSOR") (pin "B28") (pinfunction "GND_B28") (pintype "power_in"))
      (node (ref "SENSOR") (pin "B5") (pinfunction "GND_B5") (pintype "power_in"))
      (node (ref "SENSOR") (pin "C15") (pinfunction "GND_C15") (pintype "power_in"))
      (node (ref "SENSOR") (pin "C16") (pinfunction "GND_C16") (pintype "power_in"))
      (node (ref "SENSOR") (pin "C28") (pinfunction "GND_C28") (pintype "power_in"))
      (node (ref "SENSOR") (pin "D2") (pinfunction "GND_D2") (pintype "power_in"))
      (node (ref "SENSOR") (pin "D25") (pinfunction "GND_D25") (pintype "power_in"))
      (node (ref "SENSOR") (pin "D27") (pinfunction "GND_D27") (pintype "power_in"))
      (node (ref "SENSOR") (pin "D29") (pinfunction "GND_D29") (pintype "power_in"))
      (node (ref "SENSOR") (pin "E15") (pinfunction "GND_E15") (pintype "power_in"))
      (node (ref "SENSOR") (pin "E16") (pinfunction "GND_E16") (pintype "power_in"))
      (node (ref "SENSOR") (pin "E25") (pinfunction "GND_E25") (pintype "power_in"))
      (node (ref "SENSOR") (pin "E27") (pinfunction "GND_E27") (pintype "power_in"))
      (node (ref "SENSOR") (pin "E3") (pinfunction "GND_E3") (pintype "power_in"))
      (node (ref "SENSOR") (pin "F27") (pinfunction "GND_F27") (pintype "power_in"))
      (node (ref "SENSOR") (pin "G5") (pinfunction "GND_G5") (pintype "power_in"))
      (node (ref "SENSOR") (pin "H1") (pinfunction "GND_H1") (pintype "power_in"))
      (node (ref "SENSOR") (pin "H21") (pinfunction "GND_H21") (pintype "power_in"))
      (node (ref "SENSOR") (pin "H25") (pinfunction "GND_H25") (pintype "power_in"))
      (node (ref "SENSOR") (pin "H27") (pinfunction "GND_H27") (pintype "power_in"))
      (node (ref "SENSOR") (pin "H6") (pinfunction "GND_H6") (pintype "power_in"))
      (node (ref "SENSOR") (pin "H9") (pinfunction "GND_H9") (pintype "power_in"))
      (node (ref "U1") (pin "6") (pinfunction "ANODE_6") (pintype "input"))
      (node (ref "U2") (pin "6") (pinfunction "ANODE_6") (pintype "input"))
      (node (ref "U3") (pin "2") (pinfunction "GND_2") (pintype "power_in"))
      (node (ref "U3") (pin "EP") (pinfunction "EP_EP") (pintype "power_in"))
      (node (ref "U4") (pin "1") (pinfunction "~{1OE}_1") (pintype "input"))
      (node (ref "U4") (pin "10") (pinfunction "GND_10") (pintype "passive"))
      (node (ref "U4") (pin "11") (pinfunction "GND_11") (pintype "passive"))
      (node (ref "U4") (pin "16") (pinfunction "~{2OE}_16") (pintype "input"))
      (node (ref "U4") (pin "4") (pinfunction "1DIR_4") (pintype "input"))
      (node (ref "U4") (pin "9") (pinfunction "2A2_9") (pintype "output"))
      (node (ref "U5") (pin "6") (pinfunction "DIR4_6") (pintype "input"))
      (node (ref "U5") (pin "7") (pinfunction "~{OE}_7") (pintype "input"))
      (node (ref "U5") (pin "8") (pinfunction "GND_8") (pintype "passive"))
      (node (ref "U6") (pin "16") (pinfunction "DIR2_16") (pintype "input"))
      (node (ref "U6") (pin "7") (pinfunction "~{OE}_7") (pintype "input"))
      (node (ref "U6") (pin "8") (pinfunction "GND_8") (pintype "passive"))
      (node (ref "U7") (pin "4") (pinfunction "GND_4") (pintype "power_in"))
      (node (ref "U7") (pin "5") (pinfunction "A2_5") (pintype "input"))
      (node (ref "U7") (pin "6") (pinfunction "A1_6") (pintype "input"))
      (node (ref "U7") (pin "7") (pinfunction "A0_7") (pintype "input"))
      (node (ref "UEP") (pin "1") (pinfunction "A0_1") (pintype "input"))
      (node (ref "UEP") (pin "2") (pinfunction "A1_2") (pintype "input"))
      (node (ref "UEP") (pin "3") (pinfunction "A2_3") (pintype "input"))
      (node (ref "UEP") (pin "4") (pinfunction "GND_4") (pintype "passive"))
      (node (ref "UEP") (pin "EP") (pinfunction "EP_EP") (pintype "passive"))
      (node (ref "UNE") (pin "4") (pinfunction "VSS_4") (pintype "power_in"))
      (node (ref "UNE") (pin "EP") (pinfunction "EP_EP") (pintype "passive"))
      (node (ref "UNN") (pin "4") (pinfunction "VSS_4") (pintype "power_in"))
      (node (ref "UNN") (pin "EP") (pinfunction "EP_EP") (pintype "passive"))
      (node (ref "UNW") (pin "4") (pinfunction "VSS_4") (pintype "power_in"))
      (node (ref "UNW") (pin "EP") (pinfunction "EP_EP") (pintype "passive"))
      (node (ref "USE") (pin "4") (pinfunction "VSS_4") (pintype "power_in"))
      (node (ref "USE") (pin "EP") (pinfunction "EP_EP") (pintype "passive"))
      (node (ref "USS") (pin "4") (pinfunction "VSS_4") (pintype "power_in"))
      (node (ref "USS") (pin "EP") (pinfunction "EP_EP") (pintype "passive"))
      (node (ref "USW") (pin "4") (pinfunction "VSS_4") (pintype "power_in"))
      (node (ref "USW") (pin "EP") (pinfunction "EP_EP") (pintype "passive"))
      (node (ref "X-NORTH") (pin "102") (pinfunction "102_102") (pintype "bidirectional"))
      (node (ref "X-NORTH") (pin "103") (pinfunction "103_103") (pintype "bidirectional"))
      (node (ref "X-NORTH") (pin "108") (pinfunction "108_108") (pintype "bidirectional"))
      (node (ref "X-NORTH") (pin "114") (pinfunction "114_114") (pintype "bidirectional"))
      (node (ref "X-NORTH") (pin "12") (pinfunction "12_12") (pintype "bidirectional"))
      (node (ref "X-NORTH") (pin "120") (pinfunction "120_120") (pintype "bidirectional"))
      (node (ref "X-NORTH") (pin "126") (pinfunction "126_126") (pintype "bidirectional"))
      (node (ref "X-NORTH") (pin "132") (pinfunction "132_132") (pintype "bidirectional"))
      (node (ref "X-NORTH") (pin "138") (pinfunction "138_138") (pintype "bidirectional"))
      (node (ref "X-NORTH") (pin "139") (pinfunction "139_139") (pintype "bidirectional"))
      (node (ref "X-NORTH") (pin "18") (pinfunction "18_18") (pintype "bidirectional"))
      (node (ref "X-NORTH") (pin "24") (pinfunction "24_24") (pintype "bidirectional"))
      (node (ref "X-NORTH") (pin "30") (pinfunction "30_30") (pintype "bidirectional"))
      (node (ref "X-NORTH") (pin "36") (pinfunction "36_36") (pintype "bidirectional"))
      (node (ref "X-NORTH") (pin "42") (pinfunction "42_42") (pintype "bidirectional"))
      (node (ref "X-NORTH") (pin "43") (pinfunction "43_43") (pintype "bidirectional"))
      (node (ref "X-NORTH") (pin "48") (pinfunction "48_48") (pintype "bidirectional"))
      (node (ref "X-NORTH") (pin "54") (pinfunction "54_54") (pintype "bidirectional"))
      (node (ref "X-NORTH") (pin "60") (pinfunction "60_60") (pintype "bidirectional"))
      (node (ref "X-NORTH") (pin "66") (pinfunction "66_66") (pintype "bidirectional"))
      (node (ref "X-NORTH") (pin "72") (pinfunction "72_72") (pintype "bidirectional"))
      (node (ref "X-NORTH") (pin "78") (pinfunction "78_78") (pintype "bidirectional"))
      (node (ref "X-NORTH") (pin "84") (pinfunction "84_84") (pintype "bidirectional"))
      (node (ref "X-NORTH") (pin "90") (pinfunction "90_90") (pintype "bidirectional"))
      (node (ref "X-NORTH") (pin "96") (pinfunction "96_96") (pintype "bidirectional"))
      (node (ref "X-SOUTH") (pin "102") (pinfunction "102_102") (pintype "bidirectional"))
      (node (ref "X-SOUTH") (pin "103") (pinfunction "103_103") (pintype "bidirectional"))
      (node (ref "X-SOUTH") (pin "108") (pinfunction "108_108") (pintype "bidirectional"))
      (node (ref "X-SOUTH") (pin "114") (pinfunction "114_114") (pintype "bidirectional"))
      (node (ref "X-SOUTH") (pin "12") (pinfunction "12_12") (pintype "bidirectional"))
      (node (ref "X-SOUTH") (pin "120") (pinfunction "120_120") (pintype "bidirectional"))
      (node (ref "X-SOUTH") (pin "126") (pinfunction "126_126") (pintype "bidirectional"))
      (node (ref "X-SOUTH") (pin "132") (pinfunction "132_132") (pintype "bidirectional"))
      (node (ref "X-SOUTH") (pin "138") (pinfunction "138_138") (pintype "bidirectional"))
      (node (ref "X-SOUTH") (pin "139") (pinfunction "139_139") (pintype "bidirectional"))
      (node (ref "X-SOUTH") (pin "18") (pinfunction "18_18") (pintype "bidirectional"))
      (node (ref "X-SOUTH") (pin "24") (pinfunction "24_24") (pintype "bidirectional"))
      (node (ref "X-SOUTH") (pin "30") (pinfunction "30_30") (pintype "bidirectional"))
      (node (ref "X-SOUTH") (pin "36") (pinfunction "36_36") (pintype "bidirectional"))
      (node (ref "X-SOUTH") (pin "42") (pinfunction "42_42") (pintype "bidirectional"))
      (node (ref "X-SOUTH") (pin "43") (pinfunction "43_43") (pintype "bidirectional"))
      (node (ref "X-SOUTH") (pin "48") (pinfunction "48_48") (pintype "bidirectional"))
      (node (ref "X-SOUTH") (pin "54") (pinfunction "54_54") (pintype "bidirectional"))
      (node (ref "X-SOUTH") (pin "60") (pinfunction "60_60") (pintype "bidirectional"))
      (node (ref "X-SOUTH") (pin "66") (pinfunction "66_66") (pintype "bidirectional"))
      (node (ref "X-SOUTH") (pin "72") (pinfunction "72_72") (pintype "bidirectional"))
      (node (ref "X-SOUTH") (pin "78") (pinfunction "78_78") (pintype "bidirectional"))
      (node (ref "X-SOUTH") (pin "84") (pinfunction "84_84") (pintype "bidirectional"))
      (node (ref "X-SOUTH") (pin "90") (pinfunction "90_90") (pintype "bidirectional"))
      (node (ref "X-SOUTH") (pin "96") (pinfunction "96_96") (pintype "bidirectional"))
    )
    (net (code "4") (name "N$38") (class "Default")
      (node (ref "SENSOR") (pin "F4") (pinfunction "DIO1_F4") (pintype "output"))
    )
    (net (code "5") (name "N$39") (class "Default")
      (node (ref "SENSOR") (pin "E4") (pinfunction "DIO2_E4") (pintype "output"))
    )
    (net (code "6") (name "N$40") (class "Default")
      (node (ref "SENSOR") (pin "H4") (pinfunction "DIO3_H4") (pintype "output"))
    )
    (net (code "7") (name "N$41") (class "Default")
      (node (ref "SENSOR") (pin "G3") (pinfunction "DIO4_G3") (pintype "output"))
    )
    (net (code "8") (name "N$42") (class "Default")
      (node (ref "SENSOR") (pin "A2") (pinfunction "TANA_A2") (pintype "output"))
    )
    (net (code "9") (name "N00_N") (class "Default")
      (node (ref "R25") (pin "2") (pinfunction "2_2") (pintype "passive"))
      (node (ref "SENSOR") (pin "E6") (pinfunction "LVDS_CLK_P_E6") (pintype "input"))
      (node (ref "X-NORTH") (pin "16") (pinfunction "16_16") (pintype "bidirectional"))
    )
    (net (code "10") (name "N00_P") (class "Default")
      (node (ref "R25") (pin "1") (pinfunction "1_1") (pintype "passive"))
      (node (ref "SENSOR") (pin "E5") (pinfunction "LVDS_CLK_N_E5") (pintype "input"))
      (node (ref "X-NORTH") (pin "14") (pinfunction "14_14") (pintype "bidirectional"))
    )
    (net (code "11") (name "N01_N") (class "Default")
      (node (ref "SENSOR") (pin "G7") (pinfunction "OUTCLK_P_G7") (pintype "output"))
      (node (ref "X-NORTH") (pin "17") (pinfunction "17_17") (pintype "bidirectional"))
    )
    (net (code "12") (name "N01_P") (class "Default")
      (node (ref "SENSOR") (pin "G6") (pinfunction "OUTCLK_N_G6") (pintype "output"))
      (node (ref "X-NORTH") (pin "15") (pinfunction "15_15") (pintype "bidirectional"))
    )
    (net (code "13") (name "N02_N") (class "Default")
      (node (ref "SENSOR") (pin "F7") (pinfunction "OUT33_P_F7") (pintype "output"))
      (node (ref "X-NORTH") (pin "22") (pinfunction "22_22") (pintype "bidirectional"))
    )
    (net (code "14") (name "N02_P") (class "Default")
      (node (ref "SENSOR") (pin "F6") (pinfunction "OUT33_N_F6") (pintype "output"))
      (node (ref "X-NORTH") (pin "20") (pinfunction "20_20") (pintype "bidirectional"))
    )
    (net (code "15") (name "N03_N") (class "Default")
      (node (ref "X-NORTH") (pin "23") (pinfunction "23_23") (pintype "bidirectional"))
    )
    (net (code "16") (name "N03_P") (class "Default")
      (node (ref "X-NORTH") (pin "21") (pinfunction "21_21") (pintype "bidirectional"))
    )
    (net (code "17") (name "N04_N") (class "Default")
      (node (ref "SENSOR") (pin "E8") (pinfunction "OUT35_P_E8") (pintype "output"))
      (node (ref "X-NORTH") (pin "28") (pinfunction "28_28") (pintype "bidirectional"))
    )
    (net (code "18") (name "N04_P") (class "Default")
      (node (ref "SENSOR") (pin "E7") (pinfunction "OUT35_N_E7") (pintype "output"))
      (node (ref "X-NORTH") (pin "26") (pinfunction "26_26") (pintype "bidirectional"))
    )
    (net (code "19") (name "N05_N") (class "Default")
      (node (ref "SENSOR") (pin "H8") (pinfunction "OUT34_P_H8") (pintype "output"))
      (node (ref "X-NORTH") (pin "29") (pinfunction "29_29") (pintype "bidirectional"))
    )
    (net (code "20") (name "N05_P") (class "Default")
      (node (ref "SENSOR") (pin "H7") (pinfunction "OUT34_N_H7") (pintype "output"))
      (node (ref "X-NORTH") (pin "27") (pinfunction "27_27") (pintype "bidirectional"))
    )
    (net (code "21") (name "N06_N") (class "Default")
      (node (ref "SENSOR") (pin "F9") (pinfunction "OUT37_P_F9") (pintype "output"))
      (node (ref "X-NORTH") (pin "34") (pinfunction "34_34") (pintype "bidirectional"))
    )
    (net (code "22") (name "N06_P") (class "Default")
      (node (ref "SENSOR") (pin "F8") (pinfunction "OUT37_N_F8") (pintype "output"))
      (node (ref "X-NORTH") (pin "32") (pinfunction "32_32") (pintype "bidirectional"))
    )
    (net (code "23") (name "N07_N") (class "Default")
      (node (ref "SENSOR") (pin "G9") (pinfunction "OUT36_P_G9") (pintype "output"))
      (node (ref "X-NORTH") (pin "35") (pinfunction "35_35") (pintype "bidirectional"))
    )
    (net (code "24") (name "N07_P") (class "Default")
      (node (ref "SENSOR") (pin "G8") (pinfunction "OUT36_N_G8") (pintype "output"))
      (node (ref "X-NORTH") (pin "33") (pinfunction "33_33") (pintype "bidirectional"))
    )
    (net (code "25") (name "N08_N") (class "Default")
      (node (ref "SENSOR") (pin "E10") (pinfunction "OUT38_P_E10") (pintype "output"))
      (node (ref "X-NORTH") (pin "40") (pinfunction "40_40") (pintype "bidirectional"))
    )
    (net (code "26") (name "N08_P") (class "Default")
      (node (ref "SENSOR") (pin "E9") (pinfunction "OUT38_N_E9") (pintype "output"))
      (node (ref "X-NORTH") (pin "38") (pinfunction "38_38") (pintype "bidirectional"))
    )
    (net (code "27") (name "N09_N") (class "Default")
      (node (ref "SENSOR") (pin "G11") (pinfunction "OUT39_P_G11") (pintype "output"))
      (node (ref "X-NORTH") (pin "41") (pinfunction "41_41") (pintype "bidirectional"))
    )
    (net (code "28") (name "N09_P") (class "Default")
      (node (ref "SENSOR") (pin "G10") (pinfunction "OUT39_N_G10") (pintype "output"))
      (node (ref "X-NORTH") (pin "39") (pinfunction "39_39") (pintype "bidirectional"))
    )
    (net (code "29") (name "N10_N") (class "Default")
      (node (ref "SENSOR") (pin "F11") (pinfunction "OUT40_P_F11") (pintype "output"))
      (node (ref "X-NORTH") (pin "46") (pinfunction "46_46") (pintype "bidirectional"))
    )
    (net (code "30") (name "N10_P") (class "Default")
      (node (ref "SENSOR") (pin "F10") (pinfunction "OUT40_N_F10") (pintype "output"))
      (node (ref "X-NORTH") (pin "44") (pinfunction "44_44") (pintype "bidirectional"))
    )
    (net (code "31") (name "N11_N") (class "Default")
      (node (ref "SENSOR") (pin "H12") (pinfunction "OUT41_P_H12") (pintype "output"))
      (node (ref "X-NORTH") (pin "47") (pinfunction "47_47") (pintype "bidirectional"))
    )
    (net (code "32") (name "N11_P") (class "Default")
      (node (ref "SENSOR") (pin "H11") (pinfunction "OUT41_N_H11") (pintype "output"))
      (node (ref "X-NORTH") (pin "45") (pinfunction "45_45") (pintype "bidirectional"))
    )
    (net (code "33") (name "N12_N") (class "Default")
      (node (ref "SENSOR") (pin "E12") (pinfunction "OUT42_P_E12") (pintype "output"))
      (node (ref "X-NORTH") (pin "52") (pinfunction "52_52") (pintype "bidirectional"))
    )
    (net (code "34") (name "N12_P") (class "Default")
      (node (ref "SENSOR") (pin "E11") (pinfunction "OUT42_N_E11") (pintype "output"))
      (node (ref "X-NORTH") (pin "50") (pinfunction "50_50") (pintype "bidirectional"))
    )
    (net (code "35") (name "N13_N") (class "Default")
      (node (ref "SENSOR") (pin "G13") (pinfunction "OUT43_P_G13") (pintype "output"))
      (node (ref "X-NORTH") (pin "53") (pinfunction "53_53") (pintype "bidirectional"))
    )
    (net (code "36") (name "N13_P") (class "Default")
      (node (ref "SENSOR") (pin "G12") (pinfunction "OUT43_N_G12") (pintype "output"))
      (node (ref "X-NORTH") (pin "51") (pinfunction "51_51") (pintype "bidirectional"))
    )
    (net (code "37") (name "N14_N") (class "Default")
      (node (ref "SENSOR") (pin "F13") (pinfunction "OUT44_P_F13") (pintype "output"))
      (node (ref "X-NORTH") (pin "58") (pinfunction "58_58") (pintype "bidirectional"))
    )
    (net (code "38") (name "N14_P") (class "Default")
      (node (ref "SENSOR") (pin "F12") (pinfunction "OUT44_N_F12") (pintype "output"))
      (node (ref "X-NORTH") (pin "56") (pinfunction "56_56") (pintype "bidirectional"))
    )
    (net (code "39") (name "N15_N") (class "Default")
      (node (ref "SENSOR") (pin "H14") (pinfunction "OUT45_P_H14") (pintype "output"))
      (node (ref "X-NORTH") (pin "59") (pinfunction "59_59") (pintype "bidirectional"))
    )
    (net (code "40") (name "N15_P") (class "Default")
      (node (ref "SENSOR") (pin "H13") (pinfunction "OUT45_N_H13") (pintype "output"))
      (node (ref "X-NORTH") (pin "57") (pinfunction "57_57") (pintype "bidirectional"))
    )
    (net (code "41") (name "N16_N") (class "Default")
      (node (ref "SENSOR") (pin "E14") (pinfunction "OUT46_P_E14") (pintype "output"))
      (node (ref "X-NORTH") (pin "64") (pinfunction "64_64") (pintype "bidirectional"))
    )
    (net (code "42") (name "N16_P") (class "Default")
      (node (ref "SENSOR") (pin "E13") (pinfunction "OUT46_N_E13") (pintype "output"))
      (node (ref "X-NORTH") (pin "62") (pinfunction "62_62") (pintype "bidirectional"))
    )
    (net (code "43") (name "N17_N") (class "Default")
      (node (ref "SENSOR") (pin "G15") (pinfunction "OUT47_P_G15") (pintype "output"))
      (node (ref "X-NORTH") (pin "65") (pinfunction "65_65") (pintype "bidirectional"))
    )
    (net (code "44") (name "N17_P") (class "Default")
      (node (ref "SENSOR") (pin "G14") (pinfunction "OUT47_N_G14") (pintype "output"))
      (node (ref "X-NORTH") (pin "63") (pinfunction "63_63") (pintype "bidirectional"))
    )
    (net (code "45") (name "N18_N") (class "Default")
      (node (ref "SENSOR") (pin "F15") (pinfunction "OUT48_P_F15") (pintype "output"))
      (node (ref "X-NORTH") (pin "70") (pinfunction "70_70") (pintype "bidirectional"))
    )
    (net (code "46") (name "N18_P") (class "Default")
      (node (ref "SENSOR") (pin "F14") (pinfunction "OUT48_N_F14") (pintype "output"))
      (node (ref "X-NORTH") (pin "68") (pinfunction "68_68") (pintype "bidirectional"))
    )
    (net (code "47") (name "N19_N") (class "Default")
      (node (ref "SENSOR") (pin "G17") (pinfunction "OUT50_P_G17") (pintype "output"))
      (node (ref "X-NORTH") (pin "71") (pinfunction "71_71") (pintype "bidirectional"))
    )
    (net (code "48") (name "N19_P") (class "Default")
      (node (ref "SENSOR") (pin "G16") (pinfunction "OUT50_N_G16") (pintype "output"))
      (node (ref "X-NORTH") (pin "69") (pinfunction "69_69") (pintype "bidirectional"))
    )
    (net (code "49") (name "N20_N") (class "Default")
      (node (ref "SENSOR") (pin "F17") (pinfunction "OUT49_P_F17") (pintype "output"))
      (node (ref "X-NORTH") (pin "76") (pinfunction "76_76") (pintype "bidirectional"))
    )
    (net (code "50") (name "N20_P") (class "Default")
      (node (ref "SENSOR") (pin "F16") (pinfunction "OUT49_N_F16") (pintype "output"))
      (node (ref "X-NORTH") (pin "74") (pinfunction "74_74") (pintype "bidirectional"))
    )
    (net (code "51") (name "N21_N") (class "Default")
      (node (ref "SENSOR") (pin "H18") (pinfunction "OUT52_P_H18") (pintype "output"))
      (node (ref "X-NORTH") (pin "77") (pinfunction "77_77") (pintype "bidirectional"))
    )
    (net (code "52") (name "N21_P") (class "Default")
      (node (ref "SENSOR") (pin "H17") (pinfunction "OUT52_N_H17") (pintype "output"))
      (node (ref "X-NORTH") (pin "75") (pinfunction "75_75") (pintype "bidirectional"))
    )
    (net (code "53") (name "N22_N") (class "Default")
      (node (ref "SENSOR") (pin "E18") (pinfunction "OUT51_P_E18") (pintype "output"))
      (node (ref "X-NORTH") (pin "82") (pinfunction "82_82") (pintype "bidirectional"))
    )
    (net (code "54") (name "N22_P") (class "Default")
      (node (ref "SENSOR") (pin "E17") (pinfunction "OUT51_N_E17") (pintype "output"))
      (node (ref "X-NORTH") (pin "80") (pinfunction "80_80") (pintype "bidirectional"))
    )
    (net (code "55") (name "N23_N") (class "Default")
      (node (ref "SENSOR") (pin "G19") (pinfunction "OUT54_P_G19") (pintype "output"))
      (node (ref "X-NORTH") (pin "83") (pinfunction "83_83") (pintype "bidirectional"))
    )
    (net (code "56") (name "N23_P") (class "Default")
      (node (ref "SENSOR") (pin "G18") (pinfunction "OUT54_N_G18") (pintype "output"))
      (node (ref "X-NORTH") (pin "81") (pinfunction "81_81") (pintype "bidirectional"))
    )
    (net (code "57") (name "N24_N") (class "Default")
      (node (ref "SENSOR") (pin "F19") (pinfunction "OUT53_P_F19") (pintype "output"))
      (node (ref "X-NORTH") (pin "88") (pinfunction "88_88") (pintype "bidirectional"))
    )
    (net (code "58") (name "N24_P") (class "Default")
      (node (ref "SENSOR") (pin "F18") (pinfunction "OUT53_N_F18") (pintype "output"))
      (node (ref "X-NORTH") (pin "86") (pinfunction "86_86") (pintype "bidirectional"))
    )
    (net (code "59") (name "N25_N") (class "Default")
      (node (ref "SENSOR") (pin "H20") (pinfunction "OUT56_P_H20") (pintype "output"))
      (node (ref "X-NORTH") (pin "89") (pinfunction "89_89") (pintype "bidirectional"))
    )
    (net (code "60") (name "N25_P") (class "Default")
      (node (ref "SENSOR") (pin "H19") (pinfunction "OUT56_N_H19") (pintype "output"))
      (node (ref "X-NORTH") (pin "87") (pinfunction "87_87") (pintype "bidirectional"))
    )
    (net (code "61") (name "N26_N") (class "Default")
      (node (ref "SENSOR") (pin "E20") (pinfunction "OUT55_P_E20") (pintype "output"))
      (node (ref "X-NORTH") (pin "94") (pinfunction "94_94") (pintype "bidirectional"))
    )
    (net (code "62") (name "N26_P") (class "Default")
      (node (ref "SENSOR") (pin "E19") (pinfunction "OUT55_N_E19") (pintype "output"))
      (node (ref "X-NORTH") (pin "92") (pinfunction "92_92") (pintype "bidirectional"))
    )
    (net (code "63") (name "N27_N") (class "Default")
      (node (ref "SENSOR") (pin "G21") (pinfunction "OUT58_P_G21") (pintype "output"))
      (node (ref "X-NORTH") (pin "95") (pinfunction "95_95") (pintype "bidirectional"))
    )
    (net (code "64") (name "N27_P") (class "Default")
      (node (ref "SENSOR") (pin "G20") (pinfunction "OUT58_N_G20") (pintype "output"))
      (node (ref "X-NORTH") (pin "93") (pinfunction "93_93") (pintype "bidirectional"))
    )
    (net (code "65") (name "N28_N") (class "Default")
      (node (ref "SENSOR") (pin "F21") (pinfunction "OUT57_P_F21") (pintype "output"))
      (node (ref "X-NORTH") (pin "100") (pinfunction "100_100") (pintype "bidirectional"))
    )
    (net (code "66") (name "N28_P") (class "Default")
      (node (ref "SENSOR") (pin "F20") (pinfunction "OUT57_N_F20") (pintype "output"))
      (node (ref "X-NORTH") (pin "98") (pinfunction "98_98") (pintype "bidirectional"))
    )
    (net (code "67") (name "N29_N") (class "Default")
      (node (ref "SENSOR") (pin "G23") (pinfunction "OUT61_P_G23") (pintype "output"))
      (node (ref "X-NORTH") (pin "101") (pinfunction "101_101") (pintype "bidirectional"))
    )
    (net (code "68") (name "N29_P") (class "Default")
      (node (ref "SENSOR") (pin "G22") (pinfunction "OUT61_N_G22") (pintype "output"))
      (node (ref "X-NORTH") (pin "99") (pinfunction "99_99") (pintype "bidirectional"))
    )
    (net (code "69") (name "N30_N") (class "Default")
      (node (ref "SENSOR") (pin "E22") (pinfunction "OUT59_P_E22") (pintype "output"))
      (node (ref "X-NORTH") (pin "106") (pinfunction "106_106") (pintype "bidirectional"))
    )
    (net (code "70") (name "N30_P") (class "Default")
      (node (ref "SENSOR") (pin "E21") (pinfunction "OUT59_N_E21") (pintype "output"))
      (node (ref "X-NORTH") (pin "104") (pinfunction "104_104") (pintype "bidirectional"))
    )
    (net (code "71") (name "N31_N") (class "Default")
      (node (ref "SENSOR") (pin "H24") (pinfunction "OUT63_P_H24") (pintype "output"))
      (node (ref "X-NORTH") (pin "107") (pinfunction "107_107") (pintype "bidirectional"))
    )
    (net (code "72") (name "N31_P") (class "Default")
      (node (ref "SENSOR") (pin "H23") (pinfunction "OUT63_N_H23") (pintype "output"))
      (node (ref "X-NORTH") (pin "105") (pinfunction "105_105") (pintype "bidirectional"))
    )
    (net (code "73") (name "N32_N") (class "Default")
      (node (ref "SENSOR") (pin "F23") (pinfunction "OUT60_P_F23") (pintype "output"))
      (node (ref "X-NORTH") (pin "112") (pinfunction "112_112") (pintype "bidirectional"))
    )
    (net (code "74") (name "N32_P") (class "Default")
      (node (ref "SENSOR") (pin "F22") (pinfunction "OUT60_N_F22") (pintype "output"))
      (node (ref "X-NORTH") (pin "110") (pinfunction "110_110") (pintype "bidirectional"))
    )
    (net (code "75") (name "N33_N") (class "Default")
      (node (ref "SENSOR") (pin "G25") (pinfunction "OUT64_P_G25") (pintype "output"))
      (node (ref "X-NORTH") (pin "113") (pinfunction "113_113") (pintype "bidirectional"))
    )
    (net (code "76") (name "N33_P") (class "Default")
      (node (ref "SENSOR") (pin "G24") (pinfunction "OUT64_N_G24") (pintype "output"))
      (node (ref "X-NORTH") (pin "111") (pinfunction "111_111") (pintype "bidirectional"))
    )
    (net (code "77") (name "N34_N") (class "Default")
      (node (ref "SENSOR") (pin "E24") (pinfunction "OUT62_P_E24") (pintype "output"))
      (node (ref "X-NORTH") (pin "118") (pinfunction "118_118") (pintype "bidirectional"))
    )
    (net (code "78") (name "N34_P") (class "Default")
      (node (ref "SENSOR") (pin "E23") (pinfunction "OUT62_N_E23") (pintype "output"))
      (node (ref "X-NORTH") (pin "116") (pinfunction "116_116") (pintype "bidirectional"))
    )
    (net (code "79") (name "N35_N") (class "Default")
      (node (ref "U6") (pin "4") (pinfunction "A4_4") (pintype "bidirectional"))
      (node (ref "X-NORTH") (pin "119") (pinfunction "119_119") (pintype "bidirectional"))
    )
    (net (code "80") (name "N35_P") (class "Default")
      (node (ref "U6") (pin "3") (pinfunction "A3_3") (pintype "bidirectional"))
      (node (ref "X-NORTH") (pin "117") (pinfunction "117_117") (pintype "bidirectional"))
    )
    (net (code "81") (name "N36_N") (class "Default")
      (node (ref "X-NORTH") (pin "124") (pinfunction "124_124") (pintype "bidirectional"))
    )
    (net (code "82") (name "N36_P") (class "Default")
      (node (ref "X-NORTH") (pin "122") (pinfunction "122_122") (pintype "bidirectional"))
    )
    (net (code "83") (name "N37_N") (class "Default")
      (node (ref "U5") (pin "3") (pinfunction "A3_3") (pintype "bidirectional"))
      (node (ref "X-NORTH") (pin "125") (pinfunction "125_125") (pintype "bidirectional"))
    )
    (net (code "84") (name "N37_P") (class "Default")
      (node (ref "U5") (pin "4") (pinfunction "A4_4") (pintype "bidirectional"))
      (node (ref "X-NORTH") (pin "123") (pinfunction "123_123") (pintype "bidirectional"))
    )
    (net (code "85") (name "N38_N") (class "Default")
      (node (ref "U6") (pin "2") (pinfunction "A2_2") (pintype "bidirectional"))
      (node (ref "X-NORTH") (pin "130") (pinfunction "130_130") (pintype "bidirectional"))
    )
    (net (code "86") (name "N38_P") (class "Default")
      (node (ref "U6") (pin "1") (pinfunction "A1_1") (pintype "bidirectional"))
      (node (ref "X-NORTH") (pin "128") (pinfunction "128_128") (pintype "bidirectional"))
    )
    (net (code "87") (name "N39_N") (class "Default")
      (node (ref "U5") (pin "1") (pinfunction "A1_1") (pintype "bidirectional"))
      (node (ref "X-NORTH") (pin "131") (pinfunction "131_131") (pintype "bidirectional"))
    )
    (net (code "88") (name "N39_P") (class "Default")
      (node (ref "U5") (pin "2") (pinfunction "A2_2") (pintype "bidirectional"))
      (node (ref "X-NORTH") (pin "129") (pinfunction "129_129") (pintype "bidirectional"))
    )
    (net (code "89") (name "N_CHK_V") (class "Default")
      (node (ref "C2") (pin "1") (pinfunction "1_1") (pintype "passive"))
      (node (ref "C3") (pin "1") (pinfunction "1_1") (pintype "passive"))
      (node (ref "C4") (pin "1") (pinfunction "1_1") (pintype "passive"))
      (node (ref "R19") (pin "1") (pinfunction "1_1") (pintype "passive"))
      (node (ref "TP1") (pin "TP") (pinfunction "TP_TP") (pintype "input"))
      (node (ref "UNE") (pin "8") (pinfunction "VDD_8") (pintype "power_in"))
      (node (ref "UNN") (pin "8") (pinfunction "VDD_8") (pintype "power_in"))
      (node (ref "UNW") (pin "8") (pinfunction "VDD_8") (pintype "power_in"))
      (node (ref "X-NORTH") (pin "10") (pinfunction "10_10") (pintype "bidirectional"))
      (node (ref "X-NORTH") (pin "8") (pinfunction "8_8") (pintype "bidirectional"))
    )
    (net (code "90") (name "N_I2C_V") (class "Default")
      (node (ref "C1") (pin "1") (pinfunction "1_1") (pintype "passive"))
      (node (ref "R1X") (pin "1") (pinfunction "1_1") (pintype "passive"))
      (node (ref "UEP") (pin "8") (pinfunction "VCC_8") (pintype "power_in"))
      (node (ref "X-NORTH") (pin "135") (pinfunction "135_135") (pintype "bidirectional"))
      (node (ref "X-NORTH") (pin "137") (pinfunction "137_137") (pintype "bidirectional"))
    )
    (net (code "91") (name "N_REF") (class "Default")
      (node (ref "R19") (pin "2") (pinfunction "2_2") (pintype "passive"))
      (node (ref "TP2") (pin "TP") (pinfunction "TP_TP") (pintype "input"))
      (node (ref "U1") (pin "1") (pinfunction "CATHODE_1") (pintype "output"))
      (node (ref "U1") (pin "3") (pinfunction "REF_3") (pintype "input"))
      (node (ref "UNE") (pin "2") (pinfunction "VINA-_2") (pintype "input"))
      (node (ref "UNE") (pin "5") (pinfunction "VINB+_5") (pintype "input"))
      (node (ref "UNN") (pin "2") (pinfunction "VINA-_2") (pintype "input"))
      (node (ref "UNN") (pin "5") (pinfunction "VINB+_5") (pintype "input"))
      (node (ref "UNW") (pin "2") (pinfunction "VINA-_2") (pintype "input"))
      (node (ref "UNW") (pin "5") (pinfunction "VINB+_5") (pintype "input"))
    )
    (net (code "92") (name "N_SCK") (class "Default")
      (node (ref "U4") (pin "15") (pinfunction "1B1_15") (pintype "output"))
      (node (ref "X-NORTH") (pin "144") (pinfunction "144_144") (pintype "bidirectional"))
    )
    (net (code "93") (name "N_SCL") (class "Default")
      (node (ref "UEP") (pin "6") (pinfunction "SCL_6") (pintype "input"))
      (node (ref "X-NORTH") (pin "143") (pinfunction "143_143") (pintype "bidirectional"))
    )
    (net (code "94") (name "N_SDA") (class "Default")
      (node (ref "UEP") (pin "5") (pinfunction "SDA_5") (pintype "bidirectional"))
      (node (ref "X-NORTH") (pin "141") (pinfunction "141_141") (pintype "bidirectional"))
    )
    (net (code "95") (name "N_SDI") (class "Default")
      (node (ref "U4") (pin "13") (pinfunction "2B1_13") (pintype "output"))
      (node (ref "X-NORTH") (pin "140") (pinfunction "140_140") (pintype "bidirectional"))
    )
    (net (code "96") (name "N_SDO") (class "Default")
      (node (ref "U4") (pin "14") (pinfunction "1B2_14") (pintype "output"))
      (node (ref "X-NORTH") (pin "142") (pinfunction "142_142") (pintype "bidirectional"))
    )
    (net (code "97") (name "N_SPI_V") (class "Default")
      (node (ref "C59") (pin "1") (pinfunction "1_1") (pintype "passive"))
      (node (ref "U4") (pin "2") (pinfunction "VCCB_2") (pintype "power_in"))
      (node (ref "X-NORTH") (pin "134") (pinfunction "134_134") (pintype "bidirectional"))
      (node (ref "X-NORTH") (pin "136") (pinfunction "136_136") (pintype "bidirectional"))
    )
    (net (code "98") (name "N_VE") (class "Default")
      (node (ref "C50") (pin "1") (pinfunction "1_1") (pintype "passive"))
      (node (ref "C51") (pin "1") (pinfunction "1_1") (pintype "passive"))
      (node (ref "C52") (pin "1") (pinfunction "1_1") (pintype "passive"))
      (node (ref "C53") (pin "1") (pinfunction "1_1") (pintype "passive"))
      (node (ref "C54") (pin "1") (pinfunction "1_1") (pintype "passive"))
      (node (ref "C55") (pin "1") (pinfunction "1_1") (pintype "passive"))
      (node (ref "C56") (pin "1") (pinfunction "1_1") (pintype "passive"))
      (node (ref "C67") (pin "1") (pinfunction "1_1") (pintype "passive"))
      (node (ref "C69") (pin "1") (pinfunction "1_1") (pintype "passive"))
      (node (ref "C75") (pin "1") (pinfunction "1_1") (pintype "passive"))
      (node (ref "C76") (pin "1") (pinfunction "1_1") (pintype "passive"))
      (node (ref "C77") (pin "1") (pinfunction "1_1") (pintype "passive"))
      (node (ref "C84") (pin "1") (pinfunction "1_1") (pintype "passive"))
      (node (ref "C85") (pin "1") (pinfunction "1_1") (pintype "passive"))
      (node (ref "C86") (pin "1") (pinfunction "1_1") (pintype "passive"))
      (node (ref "SENSOR") (pin "C26") (pinfunction "VDD33_C26") (pintype "power_in"))
      (node (ref "SENSOR") (pin "C27") (pinfunction "VDD33_C27") (pintype "power_in"))
      (node (ref "SENSOR") (pin "D26") (pinfunction "VDD33_D26") (pintype "power_in"))
      (node (ref "SENSOR") (pin "D3") (pinfunction "VDD33_D3") (pintype "power_in"))
      (node (ref "SENSOR") (pin "E26") (pinfunction "VDD33_E26") (pintype "power_in"))
      (node (ref "SENSOR") (pin "F26") (pinfunction "VDD33_F26") (pintype "power_in"))
      (node (ref "SENSOR") (pin "F5") (pinfunction "VDD33_F5") (pintype "power_in"))
      (node (ref "TP7") (pin "TP") (pinfunction "TP_TP") (pintype "input"))
      (node (ref "U4") (pin "3") (pinfunction "VCCA_3") (pintype "power_in"))
      (node (ref "U4") (pin "5") (pinfunction "2DIR_5") (pintype "input"))
      (node (ref "U5") (pin "13") (pinfunction "VCCB_13") (pintype "power_in"))
      (node (ref "U6") (pin "13") (pinfunction "VCCB_13") (pintype "power_in"))
      (node (ref "X-NORTH") (pin "109") (pinfunction "109_109") (pintype "bidirectional"))
      (node (ref "X-NORTH") (pin "115") (pinfunction "115_115") (pintype "bidirectional"))
      (node (ref "X-NORTH") (pin "121") (pinfunction "121_121") (pintype "bidirectional"))
      (node (ref "X-NORTH") (pin "127") (pinfunction "127_127") (pintype "bidirectional"))
      (node (ref "X-NORTH") (pin "133") (pinfunction "133_133") (pintype "bidirectional"))
    )
    (net (code "99") (name "N_VE_CV") (class "Default")
      (node (ref "C10") (pin "1") (pinfunction "1_1") (pintype "passive"))
      (node (ref "R7") (pin "1") (pinfunction "1_1") (pintype "passive"))
      (node (ref "X-NORTH") (pin "6") (pinfunction "6_6") (pintype "bidirectional"))
    )
    (net (code "100") (name "N_VE_OV") (class "Default")
      (node (ref "UNE") (pin "7") (pinfunction "OUTB_7") (pintype "output"))
      (node (ref "X-NORTH") (pin "5") (pinfunction "5_5") (pintype "bidirectional"))
    )
    (net (code "101") (name "N_VE_UV") (class "Default")
      (node (ref "UNE") (pin "1") (pinfunction "OUTA_1") (pintype "output"))
      (node (ref "X-NORTH") (pin "11") (pinfunction "11_11") (pintype "bidirectional"))
    )
    (net (code "102") (name "N_VN") (class "Default")
      (node (ref "C31") (pin "1") (pinfunction "1_1") (pintype "passive"))
      (node (ref "C32") (pin "1") (pinfunction "1_1") (pintype "passive"))
      (node (ref "C33") (pin "1") (pinfunction "1_1") (pintype "passive"))
      (node (ref "C34") (pin "1") (pinfunction "1_1") (pintype "passive"))
      (node (ref "C35") (pin "1") (pinfunction "1_1") (pintype "passive"))
      (node (ref "C36") (pin "1") (pinfunction "1_1") (pintype "passive"))
      (node (ref "C37") (pin "1") (pinfunction "1_1") (pintype "passive"))
      (node (ref "C38") (pin "1") (pinfunction "1_1") (pintype "passive"))
      (node (ref "C39") (pin "1") (pinfunction "1_1") (pintype "passive"))
      (node (ref "C40") (pin "1") (pinfunction "1_1") (pintype "passive"))
      (node (ref "C41") (pin "1") (pinfunction "1_1") (pintype "passive"))
      (node (ref "C42") (pin "1") (pinfunction "1_1") (pintype "passive"))
      (node (ref "C43") (pin "1") (pinfunction "1_1") (pintype "passive"))
      (node (ref "C44") (pin "1") (pinfunction "1_1") (pintype "passive"))
      (node (ref "C68") (pin "1") (pinfunction "1_1") (pintype "passive"))
      (node (ref "C70") (pin "1") (pinfunction "1_1") (pintype "passive"))
      (node (ref "C78") (pin "1") (pinfunction "1_1") (pintype "passive"))
      (node (ref "C79") (pin "1") (pinfunction "1_1") (pintype "passive"))
      (node (ref "C80") (pin "1") (pinfunction "1_1") (pintype "passive"))
      (node (ref "C87") (pin "1") (pinfunction "1_1") (pintype "passive"))
      (node (ref "C88") (pin "1") (pinfunction "1_1") (pintype "passive"))
      (node (ref "C89") (pin "1") (pinfunction "1_1") (pintype "passive"))
      (node (ref "SENSOR") (pin "A10") (pinfunction "VDD18_A10") (pintype "power_in"))
      (node (ref "SENSOR") (pin "A15") (pinfunction "VDD18_A15") (pintype "power_in"))
      (node (ref "SENSOR") (pin "A16") (pinfunction "VDD18_A16") (pintype "power_in"))
      (node (ref "SENSOR") (pin "A22") (pinfunction "VDD18_A22") (pintype "power_in"))
      (node (ref "SENSOR") (pin "A26") (pinfunction "VDD18_A26") (pintype "power_in"))
      (node (ref "SENSOR") (pin "A27") (pinfunction "VDD18_A27") (pintype "power_in"))
      (node (ref "SENSOR") (pin "B4") (pinfunction "VDD18_B4") (pintype "power_in"))
      (node (ref "SENSOR") (pin "E1") (pinfunction "VDD18_PLL_E1") (pintype "power_in"))
      (node (ref "SENSOR") (pin "H10") (pinfunction "VDD18_H10") (pintype "power_in"))
      (node (ref "SENSOR") (pin "H15") (pinfunction "VDD18_H15") (pintype "power_in"))
      (node (ref "SENSOR") (pin "H16") (pinfunction "VDD18_H16") (pintype "power_in"))
      (node (ref "SENSOR") (pin "H22") (pinfunction "VDD18_H22") (pintype "power_in"))
      (node (ref "SENSOR") (pin "H26") (pinfunction "VDD18_H26") (pintype "power_in"))
      (node (ref "SENSOR") (pin "H5") (pinfunction "VDD18_H5") (pintype "power_in"))
      (node (ref "TP5") (pin "TP") (pinfunction "TP_TP") (pintype "input"))
      (node (ref "U5") (pin "14") (pinfunction "VCCA_14") (pintype "power_in"))
      (node (ref "U5") (pin "15") (pinfunction "DIR1_15") (pintype "input"))
      (node (ref "U5") (pin "16") (pinfunction "DIR2_16") (pintype "input"))
      (node (ref "U5") (pin "5") (pinfunction "DIR3_5") (pintype "input"))
      (node (ref "U6") (pin "14") (pinfunction "VCCA_14") (pintype "power_in"))
      (node (ref "U6") (pin "15") (pinfunction "DIR1_15") (pintype "input"))
      (node (ref "U6") (pin "5") (pinfunction "DIR3_5") (pintype "input"))
      (node (ref "U6") (pin "6") (pinfunction "DIR4_6") (pintype "input"))
      (node (ref "X-NORTH") (pin "49") (pinfunction "49_49") (pintype "bidirectional"))
      (node (ref "X-NORTH") (pin "55") (pinfunction "55_55") (pintype "bidirectional"))
      (node (ref "X-NORTH") (pin "61") (pinfunction "61_61") (pintype "bidirectional"))
      (node (ref "X-NORTH") (pin "67") (pinfunction "67_67") (pintype "bidirectional"))
      (node (ref "X-NORTH") (pin "73") (pinfunction "73_73") (pintype "bidirectional"))
      (node (ref "X-NORTH") (pin "79") (pinfunction "79_79") (pintype "bidirectional"))
      (node (ref "X-NORTH") (pin "85") (pinfunction "85_85") (pintype "bidirectional"))
      (node (ref "X-NORTH") (pin "91") (pinfunction "91_91") (pintype "bidirectional"))
      (node (ref "X-NORTH") (pin "97") (pinfunction "97_97") (pintype "bidirectional"))
    )
    (net (code "103") (name "N_VN_CV") (class "Default")
      (node (ref "C9") (pin "1") (pinfunction "1_1") (pintype "passive"))
      (node (ref "R4") (pin "1") (pinfunction "1_1") (pintype "passive"))
      (node (ref "X-NORTH") (pin "4") (pinfunction "4_4") (pintype "bidirectional"))
    )
    (net (code "104") (name "N_VN_OV") (class "Default")
      (node (ref "UNN") (pin "7") (pinfunction "OUTB_7") (pintype "output"))
      (node (ref "X-NORTH") (pin "3") (pinfunction "3_3") (pintype "bidirectional"))
    )
    (net (code "105") (name "N_VN_UV") (class "Default")
      (node (ref "UNN") (pin "1") (pinfunction "OUTA_1") (pintype "output"))
      (node (ref "X-NORTH") (pin "9") (pinfunction "9_9") (pintype "bidirectional"))
    )
    (net (code "106") (name "N_VW") (class "Default")
      (node (ref "C57") (pin "1") (pinfunction "1_1") (pintype "passive"))
      (node (ref "C58") (pin "1") (pinfunction "1_1") (pintype "passive"))
      (node (ref "C92") (pin "1") (pinfunction "1_1") (pintype "passive"))
      (node (ref "SENSOR") (pin "E2") (pinfunction "VDD_RES_E2") (pintype "power_in"))
      (node (ref "SENSOR") (pin "G4") (pinfunction "VDD_RES_G4") (pintype "power_in"))
      (node (ref "TP8") (pin "TP") (pinfunction "TP_TP") (pintype "input"))
      (node (ref "X-NORTH") (pin "13") (pinfunction "13_13") (pintype "bidirectional"))
      (node (ref "X-NORTH") (pin "19") (pinfunction "19_19") (pintype "bidirectional"))
      (node (ref "X-NORTH") (pin "25") (pinfunction "25_25") (pintype "bidirectional"))
      (node (ref "X-NORTH") (pin "31") (pinfunction "31_31") (pintype "bidirectional"))
      (node (ref "X-NORTH") (pin "37") (pinfunction "37_37") (pintype "bidirectional"))
    )
    (net (code "107") (name "N_VW_CV") (class "Default")
      (node (ref "C8") (pin "1") (pinfunction "1_1") (pintype "passive"))
      (node (ref "R1") (pin "1") (pinfunction "1_1") (pintype "passive"))
      (node (ref "X-NORTH") (pin "2") (pinfunction "2_2") (pintype "bidirectional"))
    )
    (net (code "108") (name "N_VW_OV") (class "Default")
      (node (ref "UNW") (pin "7") (pinfunction "OUTB_7") (pintype "output"))
      (node (ref "X-NORTH") (pin "1") (pinfunction "1_1") (pintype "bidirectional"))
    )
    (net (code "109") (name "N_VW_UV") (class "Default")
      (node (ref "UNW") (pin "1") (pinfunction "OUTA_1") (pintype "output"))
      (node (ref "X-NORTH") (pin "7") (pinfunction "7_7") (pintype "bidirectional"))
    )
    (net (code "110") (name "Net-(SENSORB-CMDN)") (class "Default")
      (node (ref "C61") (pin "1") (pinfunction "1_1") (pintype "passive"))
      (node (ref "SENSOR") (pin "F1") (pinfunction "CMDN_F1") (pintype "bidirectional"))
    )
    (net (code "111") (name "Net-(SENSORB-CMDP)") (class "Default")
      (node (ref "C22") (pin "2") (pinfunction "2_2") (pintype "passive"))
      (node (ref "SENSOR") (pin "F2") (pinfunction "CMDP_F2") (pintype "bidirectional"))
    )
    (net (code "112") (name "Net-(SENSORB-CMDP_COMP)") (class "Default")
      (node (ref "C28") (pin "2") (pinfunction "2_2") (pintype "passive"))
      (node (ref "SENSOR") (pin "H3") (pinfunction "CMDP_COMP_H3") (pintype "bidirectional"))
    )
    (net (code "113") (name "Net-(SENSORB-CMDP_COMP_INV)") (class "Default")
      (node (ref "C27") (pin "2") (pinfunction "2_2") (pintype "passive"))
      (node (ref "SENSOR") (pin "F3") (pinfunction "CMDP_COMP_INV_F3") (pintype "bidirectional"))
    )
    (net (code "114") (name "Net-(SENSORB-CMD_COLAMP)") (class "Default")
      (node (ref "C25") (pin "2") (pinfunction "2_2") (pintype "passive"))
      (node (ref "SENSOR") (pin "C6") (pinfunction "CMD_COLAMP_C6") (pintype "bidirectional"))
    )
    (net (code "115") (name "Net-(SENSORB-CMD_COL_LOAD)") (class "Default")
      (node (ref "C23") (pin "2") (pinfunction "2_2") (pintype "passive"))
      (node (ref "SENSOR") (pin "B1") (pinfunction "CMD_COL_LOAD_B1") (pintype "bidirectional"))
    )
    (net (code "116") (name "Net-(SENSORB-CMD_COL_PC)") (class "Default")
      (node (ref "C26") (pin "2") (pinfunction "2_2") (pintype "passive"))
      (node (ref "SENSOR") (pin "D1") (pinfunction "CMD_COL_PC_D1") (pintype "bidirectional"))
    )
    (net (code "117") (name "Net-(SENSORB-CMD_LVDS)") (class "Default")
      (node (ref "C62") (pin "1") (pinfunction "1_1") (pintype "passive"))
      (node (ref "SENSOR") (pin "C1") (pinfunction "CMD_LVDS_C1") (pintype "bidirectional"))
    )
    (net (code "118") (name "Net-(SENSORB-CMD_RAMP)") (class "Default")
      (node (ref "C24") (pin "2") (pinfunction "2_2") (pintype "passive"))
      (node (ref "SENSOR") (pin "B29") (pinfunction "CMD_RAMP_B29") (pintype "bidirectional"))
    )
    (net (code "119") (name "Net-(SENSORB-VBGAP)") (class "Default")
      (node (ref "C64") (pin "1") (pinfunction "1_1") (pintype "passive"))
      (node (ref "SENSOR") (pin "C29") (pinfunction "VBGAP_C29") (pintype "bidirectional"))
    )
    (net (code "120") (name "Net-(SENSORB-VCLAMP)") (class "Default")
      (node (ref "C63") (pin "1") (pinfunction "1_1") (pintype "passive"))
      (node (ref "SENSOR") (pin "D4") (pinfunction "VCLAMP_D4") (pintype "bidirectional"))
    )
    (net (code "121") (name "Net-(SENSORB-VCLAMP_ADC)") (class "Default")
      (node (ref "C60") (pin "1") (pinfunction "1_1") (pintype "passive"))
      (node (ref "SENSOR") (pin "G2") (pinfunction "VCLAMP_ADC_G2") (pintype "bidirectional"))
    )
    (net (code "122") (name "Net-(SENSORB-VPCH_H)") (class "Default")
      (node (ref "C71") (pin "1") (pinfunction "1_1") (pintype "passive"))
      (node (ref "SENSOR") (pin "C4") (pinfunction "VPCH_H_C4") (pintype "bidirectional"))
    )
    (net (code "123") (name "Net-(SENSORB-VPCH_L)") (class "Default")
      (node (ref "C14") (pin "1") (pinfunction "1_1") (pintype "passive"))
      (node (ref "SENSOR") (pin "A4") (pinfunction "VPCH_L_A4") (pintype "bidirectional"))
    )
    (net (code "124") (name "Net-(SENSORB-VREF)") (class "Default")
      (node (ref "C29") (pin "1") (pinfunction "1_1") (pintype "passive"))
      (node (ref "SENSOR") (pin "A3") (pinfunction "VREF_A3") (pintype "bidirectional"))
    )
    (net (code "125") (name "Net-(SENSORB-VREF_ADC)") (class "Default")
      (node (ref "C30") (pin "1") (pinfunction "1_1") (pintype "passive"))
      (node (ref "SENSOR") (pin "B3") (pinfunction "VREF_ADC_B3") (pintype "bidirectional"))
    )
    (net (code "126") (name "Net-(SENSORB-VRES_L)") (class "Default")
      (node (ref "C15") (pin "1") (pinfunction "1_1") (pintype "passive"))
      (node (ref "SENSOR") (pin "D5") (pinfunction "VRES_L_D5") (pintype "bidirectional"))
    )
    (net (code "127") (name "Net-(SENSORB-VTF_LOW0)") (class "Default")
      (node (ref "C18") (pin "1") (pinfunction "1_1") (pintype "passive"))
      (node (ref "SENSOR") (pin "C5") (pinfunction "VTF_LOW0_C5") (pintype "bidirectional"))
    )
    (net (code "128") (name "Net-(SENSORB-VTF_LOW1)") (class "Default")
      (node (ref "C19") (pin "1") (pinfunction "1_1") (pintype "passive"))
      (node (ref "SENSOR") (pin "D6") (pinfunction "VTF_LOW1_D6") (pintype "bidirectional"))
    )
    (net (code "129") (name "Net-(SENSORB-VTF_LOW2)") (class "Default")
      (node (ref "C20") (pin "1") (pinfunction "1_1") (pintype "passive"))
      (node (ref "SENSOR") (pin "B30") (pinfunction "VTF_LOW2_B30") (pintype "bidirectional"))
    )
    (net (code "130") (name "Net-(SENSORB-VTF_LOW3)") (class "Default")
      (node (ref "C21") (pin "1") (pinfunction "1_1") (pintype "passive"))
      (node (ref "SENSOR") (pin "C30") (pinfunction "VTF_LOW3_C30") (pintype "bidirectional"))
    )
    (net (code "131") (name "Net-(U3-ADJ)") (class "Default")
      (node (ref "R21") (pin "1") (pinfunction "1_1") (pintype "passive"))
      (node (ref "R22") (pin "2") (pinfunction "2_2") (pintype "passive"))
      (node (ref "U3") (pin "5") (pinfunction "ADJ_5") (pintype "input"))
    )
    (net (code "132") (name "Net-(UEP-WP)") (class "Default")
      (node (ref "R1X") (pin "2") (pinfunction "2_2") (pintype "passive"))
      (node (ref "R2X") (pin "1") (pinfunction "1_1") (pintype "passive"))
      (node (ref "UEP") (pin "7") (pinfunction "WP_7") (pintype "input"))
    )
    (net (code "133") (name "Net-(UNE-VINA+)") (class "Default")
      (node (ref "R7") (pin "2") (pinfunction "2_2") (pintype "passive"))
      (node (ref "R8") (pin "1") (pinfunction "1_1") (pintype "passive"))
      (node (ref "UNE") (pin "3") (pinfunction "VINA+_3") (pintype "input"))
    )
    (net (code "134") (name "Net-(UNE-VINB-)") (class "Default")
      (node (ref "R8") (pin "2") (pinfunction "2_2") (pintype "passive"))
      (node (ref "R9") (pin "1") (pinfunction "1_1") (pintype "passive"))
      (node (ref "UNE") (pin "6") (pinfunction "VINB-_6") (pintype "input"))
    )
    (net (code "135") (name "Net-(UNN-VINA+)") (class "Default")
      (node (ref "R4") (pin "2") (pinfunction "2_2") (pintype "passive"))
      (node (ref "R5") (pin "1") (pinfunction "1_1") (pintype "passive"))
      (node (ref "UNN") (pin "3") (pinfunction "VINA+_3") (pintype "input"))
    )
    (net (code "136") (name "Net-(UNN-VINB-)") (class "Default")
      (node (ref "R5") (pin "2") (pinfunction "2_2") (pintype "passive"))
      (node (ref "R6") (pin "1") (pinfunction "1_1") (pintype "passive"))
      (node (ref "UNN") (pin "6") (pinfunction "VINB-_6") (pintype "input"))
    )
    (net (code "137") (name "Net-(UNW-VINA+)") (class "Default")
      (node (ref "R1") (pin "2") (pinfunction "2_2") (pintype "passive"))
      (node (ref "R2") (pin "1") (pinfunction "1_1") (pintype "passive"))
      (node (ref "UNW") (pin "3") (pinfunction "VINA+_3") (pintype "input"))
    )
    (net (code "138") (name "Net-(UNW-VINB-)") (class "Default")
      (node (ref "R2") (pin "2") (pinfunction "2_2") (pintype "passive"))
      (node (ref "R3") (pin "1") (pinfunction "1_1") (pintype "passive"))
      (node (ref "UNW") (pin "6") (pinfunction "VINB-_6") (pintype "input"))
    )
    (net (code "139") (name "Net-(USE-VINA+)") (class "Default")
      (node (ref "R10") (pin "2") (pinfunction "2_2") (pintype "passive"))
      (node (ref "R11") (pin "1") (pinfunction "1_1") (pintype "passive"))
      (node (ref "USE") (pin "3") (pinfunction "VINA+_3") (pintype "input"))
    )
    (net (code "140") (name "Net-(USE-VINB-)") (class "Default")
      (node (ref "R11") (pin "2") (pinfunction "2_2") (pintype "passive"))
      (node (ref "R12") (pin "1") (pinfunction "1_1") (pintype "passive"))
      (node (ref "USE") (pin "6") (pinfunction "VINB-_6") (pintype "input"))
    )
    (net (code "141") (name "Net-(USS-VINA+)") (class "Default")
      (node (ref "R13") (pin "2") (pinfunction "2_2") (pintype "passive"))
      (node (ref "R14") (pin "1") (pinfunction "1_1") (pintype "passive"))
      (node (ref "USS") (pin "3") (pinfunction "VINA+_3") (pintype "input"))
    )
    (net (code "142") (name "Net-(USS-VINB-)") (class "Default")
      (node (ref "R14") (pin "2") (pinfunction "2_2") (pintype "passive"))
      (node (ref "R15") (pin "1") (pinfunction "1_1") (pintype "passive"))
      (node (ref "USS") (pin "6") (pinfunction "VINB-_6") (pintype "input"))
    )
    (net (code "143") (name "Net-(USW-VINA+)") (class "Default")
      (node (ref "R16") (pin "2") (pinfunction "2_2") (pintype "passive"))
      (node (ref "R17") (pin "1") (pinfunction "1_1") (pintype "passive"))
      (node (ref "USW") (pin "3") (pinfunction "VINA+_3") (pintype "input"))
    )
    (net (code "144") (name "Net-(USW-VINB-)") (class "Default")
      (node (ref "R17") (pin "2") (pinfunction "2_2") (pintype "passive"))
      (node (ref "R18") (pin "1") (pinfunction "1_1") (pintype "passive"))
      (node (ref "USW") (pin "6") (pinfunction "VINB-_6") (pintype "input"))
    )
    (net (code "145") (name "S00_N") (class "Default")
      (node (ref "X-SOUTH") (pin "16") (pinfunction "16_16") (pintype "bidirectional"))
    )
    (net (code "146") (name "S00_P") (class "Default")
      (node (ref "X-SOUTH") (pin "14") (pinfunction "14_14") (pintype "bidirectional"))
    )
    (net (code "147") (name "S01_N") (class "Default")
      (node (ref "X-SOUTH") (pin "17") (pinfunction "17_17") (pintype "bidirectional"))
    )
    (net (code "148") (name "S01_P") (class "Default")
      (node (ref "X-SOUTH") (pin "15") (pinfunction "15_15") (pintype "bidirectional"))
    )
    (net (code "149") (name "S02_N") (class "Default")
      (node (ref "X-SOUTH") (pin "22") (pinfunction "22_22") (pintype "bidirectional"))
    )
    (net (code "150") (name "S02_P") (class "Default")
      (node (ref "X-SOUTH") (pin "20") (pinfunction "20_20") (pintype "bidirectional"))
    )
    (net (code "151") (name "S03_N") (class "Default")
      (node (ref "X-SOUTH") (pin "23") (pinfunction "23_23") (pintype "bidirectional"))
    )
    (net (code "152") (name "S03_P") (class "Default")
      (node (ref "X-SOUTH") (pin "21") (pinfunction "21_21") (pintype "bidirectional"))
    )
    (net (code "153") (name "S04_N") (class "Default")
      (node (ref "SENSOR") (pin "C24") (pinfunction "OUT32_N_C24") (pintype "output"))
      (node (ref "X-SOUTH") (pin "28") (pinfunction "28_28") (pintype "bidirectional"))
    )
    (net (code "154") (name "S04_P") (class "Default")
      (node (ref "SENSOR") (pin "C25") (pinfunction "OUT32_P_C25") (pintype "output"))
      (node (ref "X-SOUTH") (pin "26") (pinfunction "26_26") (pintype "bidirectional"))
    )
    (net (code "155") (name "S05_N") (class "Default")
      (node (ref "X-SOUTH") (pin "29") (pinfunction "29_29") (pintype "bidirectional"))
    )
    (net (code "156") (name "S05_P") (class "Default")
      (node (ref "X-SOUTH") (pin "27") (pinfunction "27_27") (pintype "bidirectional"))
    )
    (net (code "157") (name "S06_N") (class "Default")
      (node (ref "SENSOR") (pin "D23") (pinfunction "OUT30_N_D23") (pintype "output"))
      (node (ref "X-SOUTH") (pin "34") (pinfunction "34_34") (pintype "bidirectional"))
    )
    (net (code "158") (name "S06_P") (class "Default")
      (node (ref "SENSOR") (pin "D24") (pinfunction "OUT30_P_D24") (pintype "output"))
      (node (ref "X-SOUTH") (pin "32") (pinfunction "32_32") (pintype "bidirectional"))
    )
    (net (code "159") (name "S07_N") (class "Default")
      (node (ref "SENSOR") (pin "B24") (pinfunction "OUT31_N_B24") (pintype "output"))
      (node (ref "X-SOUTH") (pin "35") (pinfunction "35_35") (pintype "bidirectional"))
    )
    (net (code "160") (name "S07_P") (class "Default")
      (node (ref "SENSOR") (pin "B25") (pinfunction "OUT31_P_B25") (pintype "output"))
      (node (ref "X-SOUTH") (pin "33") (pinfunction "33_33") (pintype "bidirectional"))
    )
    (net (code "161") (name "S08_N") (class "Default")
      (node (ref "SENSOR") (pin "D21") (pinfunction "OUT27_N_D21") (pintype "output"))
      (node (ref "X-SOUTH") (pin "40") (pinfunction "40_40") (pintype "bidirectional"))
    )
    (net (code "162") (name "S08_P") (class "Default")
      (node (ref "SENSOR") (pin "D22") (pinfunction "OUT27_P_D22") (pintype "output"))
      (node (ref "X-SOUTH") (pin "38") (pinfunction "38_38") (pintype "bidirectional"))
    )
    (net (code "163") (name "S09_N") (class "Default")
      (node (ref "SENSOR") (pin "A23") (pinfunction "OUT29_N_A23") (pintype "output"))
      (node (ref "X-SOUTH") (pin "41") (pinfunction "41_41") (pintype "bidirectional"))
    )
    (net (code "164") (name "S09_P") (class "Default")
      (node (ref "SENSOR") (pin "A24") (pinfunction "OUT29_P_A24") (pintype "output"))
      (node (ref "X-SOUTH") (pin "39") (pinfunction "39_39") (pintype "bidirectional"))
    )
    (net (code "165") (name "S10_N") (class "Default")
      (node (ref "SENSOR") (pin "C21") (pinfunction "OUT28_N_C21") (pintype "output"))
      (node (ref "X-SOUTH") (pin "46") (pinfunction "46_46") (pintype "bidirectional"))
    )
    (net (code "166") (name "S10_P") (class "Default")
      (node (ref "SENSOR") (pin "C22") (pinfunction "OUT28_P_C22") (pintype "output"))
      (node (ref "X-SOUTH") (pin "44") (pinfunction "44_44") (pintype "bidirectional"))
    )
    (net (code "167") (name "S11_N") (class "Default")
      (node (ref "SENSOR") (pin "B20") (pinfunction "OUT26_N_B20") (pintype "output"))
      (node (ref "X-SOUTH") (pin "47") (pinfunction "47_47") (pintype "bidirectional"))
    )
    (net (code "168") (name "S11_P") (class "Default")
      (node (ref "SENSOR") (pin "B21") (pinfunction "OUT26_P_B21") (pintype "output"))
      (node (ref "X-SOUTH") (pin "45") (pinfunction "45_45") (pintype "bidirectional"))
    )
    (net (code "169") (name "S12_N") (class "Default")
      (node (ref "SENSOR") (pin "D19") (pinfunction "OUT24_N_D19") (pintype "output"))
      (node (ref "X-SOUTH") (pin "52") (pinfunction "52_52") (pintype "bidirectional"))
    )
    (net (code "170") (name "S12_P") (class "Default")
      (node (ref "SENSOR") (pin "D20") (pinfunction "OUT24_P_D20") (pintype "output"))
      (node (ref "X-SOUTH") (pin "50") (pinfunction "50_50") (pintype "bidirectional"))
    )
    (net (code "171") (name "S13_N") (class "Default")
      (node (ref "SENSOR") (pin "A19") (pinfunction "OUT23_N_A19") (pintype "output"))
      (node (ref "X-SOUTH") (pin "53") (pinfunction "53_53") (pintype "bidirectional"))
    )
    (net (code "172") (name "S13_P") (class "Default")
      (node (ref "SENSOR") (pin "A20") (pinfunction "OUT23_P_A20") (pintype "output"))
      (node (ref "X-SOUTH") (pin "51") (pinfunction "51_51") (pintype "bidirectional"))
    )
    (net (code "173") (name "S14_N") (class "Default")
      (node (ref "SENSOR") (pin "C19") (pinfunction "OUT25_N_C19") (pintype "output"))
      (node (ref "X-SOUTH") (pin "58") (pinfunction "58_58") (pintype "bidirectional"))
    )
    (net (code "174") (name "S14_P") (class "Default")
      (node (ref "SENSOR") (pin "C20") (pinfunction "OUT25_P_C20") (pintype "output"))
      (node (ref "X-SOUTH") (pin "56") (pinfunction "56_56") (pintype "bidirectional"))
    )
    (net (code "175") (name "S15_N") (class "Default")
      (node (ref "SENSOR") (pin "B18") (pinfunction "OUT22_N_B18") (pintype "output"))
      (node (ref "X-SOUTH") (pin "59") (pinfunction "59_59") (pintype "bidirectional"))
    )
    (net (code "176") (name "S15_P") (class "Default")
      (node (ref "SENSOR") (pin "B19") (pinfunction "OUT22_P_B19") (pintype "output"))
      (node (ref "X-SOUTH") (pin "57") (pinfunction "57_57") (pintype "bidirectional"))
    )
    (net (code "177") (name "S16_N") (class "Default")
      (node (ref "SENSOR") (pin "C17") (pinfunction "OUT21_N_C17") (pintype "output"))
      (node (ref "X-SOUTH") (pin "64") (pinfunction "64_64") (pintype "bidirectional"))
    )
    (net (code "178") (name "S16_P") (class "Default")
      (node (ref "SENSOR") (pin "C18") (pinfunction "OUT21_P_C18") (pintype "output"))
      (node (ref "X-SOUTH") (pin "62") (pinfunction "62_62") (pintype "bidirectional"))
    )
    (net (code "179") (name "S17_N") (class "Default")
      (node (ref "SENSOR") (pin "A17") (pinfunction "OUT19_N_A17") (pintype "output"))
      (node (ref "X-SOUTH") (pin "65") (pinfunction "65_65") (pintype "bidirectional"))
    )
    (net (code "180") (name "S17_P") (class "Default")
      (node (ref "SENSOR") (pin "A18") (pinfunction "OUT19_P_A18") (pintype "output"))
      (node (ref "X-SOUTH") (pin "63") (pinfunction "63_63") (pintype "bidirectional"))
    )
    (net (code "181") (name "S18_N") (class "Default")
      (node (ref "SENSOR") (pin "D17") (pinfunction "OUT20_N_D17") (pintype "output"))
      (node (ref "X-SOUTH") (pin "70") (pinfunction "70_70") (pintype "bidirectional"))
    )
    (net (code "182") (name "S18_P") (class "Default")
      (node (ref "SENSOR") (pin "D18") (pinfunction "OUT20_P_D18") (pintype "output"))
      (node (ref "X-SOUTH") (pin "68") (pinfunction "68_68") (pintype "bidirectional"))
    )
    (net (code "183") (name "S19_N") (class "Default")
      (node (ref "SENSOR") (pin "B16") (pinfunction "OUT18_N_B16") (pintype "output"))
      (node (ref "X-SOUTH") (pin "71") (pinfunction "71_71") (pintype "bidirectional"))
    )
    (net (code "184") (name "S19_P") (class "Default")
      (node (ref "SENSOR") (pin "B17") (pinfunction "OUT18_P_B17") (pintype "output"))
      (node (ref "X-SOUTH") (pin "69") (pinfunction "69_69") (pintype "bidirectional"))
    )
    (net (code "185") (name "S20_N") (class "Default")
      (node (ref "SENSOR") (pin "D15") (pinfunction "OUT17_N_D15") (pintype "output"))
      (node (ref "X-SOUTH") (pin "76") (pinfunction "76_76") (pintype "bidirectional"))
    )
    (net (code "186") (name "S20_P") (class "Default")
      (node (ref "SENSOR") (pin "D16") (pinfunction "OUT17_P_D16") (pintype "output"))
      (node (ref "X-SOUTH") (pin "74") (pinfunction "74_74") (pintype "bidirectional"))
    )
    (net (code "187") (name "S21_N") (class "Default")
      (node (ref "SENSOR") (pin "B14") (pinfunction "OUT16_N_B14") (pintype "output"))
      (node (ref "X-SOUTH") (pin "77") (pinfunction "77_77") (pintype "bidirectional"))
    )
    (net (code "188") (name "S21_P") (class "Default")
      (node (ref "SENSOR") (pin "B15") (pinfunction "OUT16_P_B15") (pintype "output"))
      (node (ref "X-SOUTH") (pin "75") (pinfunction "75_75") (pintype "bidirectional"))
    )
    (net (code "189") (name "S22_N") (class "Default")
      (node (ref "SENSOR") (pin "D13") (pinfunction "OUT15_N_D13") (pintype "output"))
      (node (ref "X-SOUTH") (pin "82") (pinfunction "82_82") (pintype "bidirectional"))
    )
    (net (code "190") (name "S22_P") (class "Default")
      (node (ref "SENSOR") (pin "D14") (pinfunction "OUT15_P_D14") (pintype "output"))
      (node (ref "X-SOUTH") (pin "80") (pinfunction "80_80") (pintype "bidirectional"))
    )
    (net (code "191") (name "S23_N") (class "Default")
      (node (ref "SENSOR") (pin "A13") (pinfunction "OUT13_N_A13") (pintype "output"))
      (node (ref "X-SOUTH") (pin "83") (pinfunction "83_83") (pintype "bidirectional"))
    )
    (net (code "192") (name "S23_P") (class "Default")
      (node (ref "SENSOR") (pin "A14") (pinfunction "OUT13_P_A14") (pintype "output"))
      (node (ref "X-SOUTH") (pin "81") (pinfunction "81_81") (pintype "bidirectional"))
    )
    (net (code "193") (name "S24_N") (class "Default")
      (node (ref "SENSOR") (pin "C13") (pinfunction "OUT14_N_C13") (pintype "output"))
      (node (ref "X-SOUTH") (pin "88") (pinfunction "88_88") (pintype "bidirectional"))
    )
    (net (code "194") (name "S24_P") (class "Default")
      (node (ref "SENSOR") (pin "C14") (pinfunction "OUT14_P_C14") (pintype "output"))
      (node (ref "X-SOUTH") (pin "86") (pinfunction "86_86") (pintype "bidirectional"))
    )
    (net (code "195") (name "S25_N") (class "Default")
      (node (ref "SENSOR") (pin "B12") (pinfunction "OUT12_N_B12") (pintype "output"))
      (node (ref "X-SOUTH") (pin "89") (pinfunction "89_89") (pintype "bidirectional"))
    )
    (net (code "196") (name "S25_P") (class "Default")
      (node (ref "SENSOR") (pin "B13") (pinfunction "OUT12_P_B13") (pintype "output"))
      (node (ref "X-SOUTH") (pin "87") (pinfunction "87_87") (pintype "bidirectional"))
    )
    (net (code "197") (name "S26_N") (class "Default")
      (node (ref "SENSOR") (pin "D11") (pinfunction "OUT10_N_D11") (pintype "output"))
      (node (ref "X-SOUTH") (pin "94") (pinfunction "94_94") (pintype "bidirectional"))
    )
    (net (code "198") (name "S26_P") (class "Default")
      (node (ref "SENSOR") (pin "D12") (pinfunction "OUT10_P_D12") (pintype "output"))
      (node (ref "X-SOUTH") (pin "92") (pinfunction "92_92") (pintype "bidirectional"))
    )
    (net (code "199") (name "S27_N") (class "Default")
      (node (ref "SENSOR") (pin "A11") (pinfunction "OUT9_N_A11") (pintype "output"))
      (node (ref "X-SOUTH") (pin "95") (pinfunction "95_95") (pintype "bidirectional"))
    )
    (net (code "200") (name "S27_P") (class "Default")
      (node (ref "SENSOR") (pin "A12") (pinfunction "OUT9_P_A12") (pintype "output"))
      (node (ref "X-SOUTH") (pin "93") (pinfunction "93_93") (pintype "bidirectional"))
    )
    (net (code "201") (name "S28_N") (class "Default")
      (node (ref "SENSOR") (pin "C11") (pinfunction "OUT11_N_C11") (pintype "output"))
      (node (ref "X-SOUTH") (pin "100") (pinfunction "100_100") (pintype "bidirectional"))
    )
    (net (code "202") (name "S28_P") (class "Default")
      (node (ref "SENSOR") (pin "C12") (pinfunction "OUT11_P_C12") (pintype "output"))
      (node (ref "X-SOUTH") (pin "98") (pinfunction "98_98") (pintype "bidirectional"))
    )
    (net (code "203") (name "S29_N") (class "Default")
      (node (ref "SENSOR") (pin "B10") (pinfunction "OUT8_N_B10") (pintype "output"))
      (node (ref "X-SOUTH") (pin "101") (pinfunction "101_101") (pintype "bidirectional"))
    )
    (net (code "204") (name "S29_P") (class "Default")
      (node (ref "SENSOR") (pin "B11") (pinfunction "OUT8_P_B11") (pintype "output"))
      (node (ref "X-SOUTH") (pin "99") (pinfunction "99_99") (pintype "bidirectional"))
    )
    (net (code "205") (name "S30_N") (class "Default")
      (node (ref "SENSOR") (pin "C9") (pinfunction "OUT7_N_C9") (pintype "output"))
      (node (ref "X-SOUTH") (pin "106") (pinfunction "106_106") (pintype "bidirectional"))
    )
    (net (code "206") (name "S30_P") (class "Default")
      (node (ref "SENSOR") (pin "C10") (pinfunction "OUT7_P_C10") (pintype "output"))
      (node (ref "X-SOUTH") (pin "104") (pinfunction "104_104") (pintype "bidirectional"))
    )
    (net (code "207") (name "S31_N") (class "Default")
      (node (ref "SENSOR") (pin "B8") (pinfunction "OUT5_N_B8") (pintype "output"))
      (node (ref "X-SOUTH") (pin "107") (pinfunction "107_107") (pintype "bidirectional"))
    )
    (net (code "208") (name "S31_P") (class "Default")
      (node (ref "SENSOR") (pin "B9") (pinfunction "OUT5_P_B9") (pintype "output"))
      (node (ref "X-SOUTH") (pin "105") (pinfunction "105_105") (pintype "bidirectional"))
    )
    (net (code "209") (name "S32_N") (class "Default")
      (node (ref "SENSOR") (pin "D9") (pinfunction "OUT6_N_D9") (pintype "output"))
      (node (ref "X-SOUTH") (pin "112") (pinfunction "112_112") (pintype "bidirectional"))
    )
    (net (code "210") (name "S32_P") (class "Default")
      (node (ref "SENSOR") (pin "D10") (pinfunction "OUT6_P_D10") (pintype "output"))
      (node (ref "X-SOUTH") (pin "110") (pinfunction "110_110") (pintype "bidirectional"))
    )
    (net (code "211") (name "S33_N") (class "Default")
      (node (ref "SENSOR") (pin "A7") (pinfunction "OUT2_N_A7") (pintype "output"))
      (node (ref "X-SOUTH") (pin "113") (pinfunction "113_113") (pintype "bidirectional"))
    )
    (net (code "212") (name "S33_P") (class "Default")
      (node (ref "SENSOR") (pin "A8") (pinfunction "OUT2_P_A8") (pintype "output"))
      (node (ref "X-SOUTH") (pin "111") (pinfunction "111_111") (pintype "bidirectional"))
    )
    (net (code "213") (name "S34_N") (class "Default")
      (node (ref "SENSOR") (pin "C7") (pinfunction "OUT4_N_C7") (pintype "output"))
      (node (ref "X-SOUTH") (pin "118") (pinfunction "118_118") (pintype "bidirectional"))
    )
    (net (code "214") (name "S34_P") (class "Default")
      (node (ref "SENSOR") (pin "C8") (pinfunction "OUT4_P_C8") (pintype "output"))
      (node (ref "X-SOUTH") (pin "116") (pinfunction "116_116") (pintype "bidirectional"))
    )
    (net (code "215") (name "S35_N") (class "Default")
      (node (ref "SENSOR") (pin "B6") (pinfunction "OUT1_N_B6") (pintype "output"))
      (node (ref "X-SOUTH") (pin "119") (pinfunction "119_119") (pintype "bidirectional"))
    )
    (net (code "216") (name "S35_P") (class "Default")
      (node (ref "SENSOR") (pin "B7") (pinfunction "OUT1_P_B7") (pintype "output"))
      (node (ref "X-SOUTH") (pin "117") (pinfunction "117_117") (pintype "bidirectional"))
    )
    (net (code "217") (name "S36_N") (class "Default")
      (node (ref "SENSOR") (pin "D7") (pinfunction "OUT3_N_D7") (pintype "output"))
      (node (ref "X-SOUTH") (pin "124") (pinfunction "124_124") (pintype "bidirectional"))
    )
    (net (code "218") (name "S36_P") (class "Default")
      (node (ref "SENSOR") (pin "D8") (pinfunction "OUT3_P_D8") (pintype "output"))
      (node (ref "X-SOUTH") (pin "122") (pinfunction "122_122") (pintype "bidirectional"))
    )
    (net (code "219") (name "S37_N") (class "Default")
      (node (ref "SENSOR") (pin "A5") (pinfunction "OUTCTR_N_A5") (pintype "output"))
      (node (ref "X-SOUTH") (pin "125") (pinfunction "125_125") (pintype "bidirectional"))
    )
    (net (code "220") (name "S37_P") (class "Default")
      (node (ref "SENSOR") (pin "A6") (pinfunction "OUTCTR_P_A6") (pintype "output"))
      (node (ref "X-SOUTH") (pin "123") (pinfunction "123_123") (pintype "bidirectional"))
    )
    (net (code "221") (name "S38_N") (class "Default")
      (node (ref "X-SOUTH") (pin "130") (pinfunction "130_130") (pintype "bidirectional"))
    )
    (net (code "222") (name "S38_P") (class "Default")
      (node (ref "X-SOUTH") (pin "128") (pinfunction "128_128") (pintype "bidirectional"))
    )
    (net (code "223") (name "S39_N") (class "Default")
      (node (ref "U3") (pin "6") (pinfunction "EN_6") (pintype "input"))
      (node (ref "X-SOUTH") (pin "131") (pinfunction "131_131") (pintype "bidirectional"))
    )
    (net (code "224") (name "S39_P") (class "Default")
      (node (ref "X-SOUTH") (pin "129") (pinfunction "129_129") (pintype "bidirectional"))
    )
    (net (code "225") (name "SPI_CLK") (class "Default")
      (node (ref "SENSOR") (pin "H29") (pinfunction "SPI_CLK_H29") (pintype "input"))
      (node (ref "U4") (pin "6") (pinfunction "1A1_6") (pintype "output"))
    )
    (net (code "226") (name "SPI_EN") (class "Default")
      (node (ref "SENSOR") (pin "F28") (pinfunction "SPI_EN_F28") (pintype "input"))
      (node (ref "U6") (pin "9") (pinfunction "B4_9") (pintype "bidirectional"))
    )
    (net (code "227") (name "SPI_IN") (class "Default")
      (node (ref "SENSOR") (pin "E28") (pinfunction "SPI_IN_E28") (pintype "input"))
      (node (ref "U4") (pin "7") (pinfunction "1A2_7") (pintype "output"))
    )
    (net (code "228") (name "SPI_OUT") (class "Default")
      (node (ref "SENSOR") (pin "G28") (pinfunction "SPI_OUT_G28") (pintype "output"))
      (node (ref "U4") (pin "8") (pinfunction "2A1_8") (pintype "output"))
    )
    (net (code "229") (name "SYS_RES_N") (class "Default")
      (node (ref "SENSOR") (pin "F30") (pinfunction "SYS_RES_N_F30") (pintype "input"))
      (node (ref "U5") (pin "10") (pinfunction "B3_10") (pintype "bidirectional"))
    )
    (net (code "230") (name "S_CHK_V") (class "Default")
      (node (ref "C5") (pin "1") (pinfunction "1_1") (pintype "passive"))
      (node (ref "C6") (pin "1") (pinfunction "1_1") (pintype "passive"))
      (node (ref "C7") (pin "1") (pinfunction "1_1") (pintype "passive"))
      (node (ref "R20") (pin "1") (pinfunction "1_1") (pintype "passive"))
      (node (ref "TP3") (pin "TP") (pinfunction "TP_TP") (pintype "input"))
      (node (ref "USE") (pin "8") (pinfunction "VDD_8") (pintype "power_in"))
      (node (ref "USS") (pin "8") (pinfunction "VDD_8") (pintype "power_in"))
      (node (ref "USW") (pin "8") (pinfunction "VDD_8") (pintype "power_in"))
      (node (ref "X-SOUTH") (pin "10") (pinfunction "10_10") (pintype "bidirectional"))
      (node (ref "X-SOUTH") (pin "8") (pinfunction "8_8") (pintype "bidirectional"))
    )
    (net (code "231") (name "S_I2C_V") (class "Default")
      (node (ref "U7") (pin "8") (pinfunction "VCC_8") (pintype "power_in"))
      (node (ref "X-SOUTH") (pin "135") (pinfunction "135_135") (pintype "bidirectional"))
      (node (ref "X-SOUTH") (pin "137") (pinfunction "137_137") (pintype "bidirectional"))
    )
    (net (code "232") (name "S_REF") (class "Default")
      (node (ref "R20") (pin "2") (pinfunction "2_2") (pintype "passive"))
      (node (ref "TP4") (pin "TP") (pinfunction "TP_TP") (pintype "input"))
      (node (ref "U2") (pin "1") (pinfunction "CATHODE_1") (pintype "output"))
      (node (ref "U2") (pin "3") (pinfunction "REF_3") (pintype "input"))
      (node (ref "USE") (pin "2") (pinfunction "VINA-_2") (pintype "input"))
      (node (ref "USE") (pin "5") (pinfunction "VINB+_5") (pintype "input"))
      (node (ref "USS") (pin "2") (pinfunction "VINA-_2") (pintype "input"))
      (node (ref "USS") (pin "5") (pinfunction "VINB+_5") (pintype "input"))
      (node (ref "USW") (pin "2") (pinfunction "VINA-_2") (pintype "input"))
      (node (ref "USW") (pin "5") (pinfunction "VINB+_5") (pintype "input"))
    )
    (net (code "233") (name "S_SCK") (class "Default")
      (node (ref "X-SOUTH") (pin "144") (pinfunction "144_144") (pintype "bidirectional"))
    )
    (net (code "234") (name "S_SCL") (class "Default")
      (node (ref "U7") (pin "2") (pinfunction "SCL_2") (pintype "input"))
      (node (ref "X-SOUTH") (pin "143") (pinfunction "143_143") (pintype "bidirectional"))
    )
    (net (code "235") (name "S_SDA") (class "Default")
      (node (ref "U7") (pin "1") (pinfunction "SDA_1") (pintype "bidirectional"))
      (node (ref "X-SOUTH") (pin "141") (pinfunction "141_141") (pintype "bidirectional"))
    )
    (net (code "236") (name "S_SDI") (class "Default")
      (node (ref "X-SOUTH") (pin "140") (pinfunction "140_140") (pintype "bidirectional"))
    )
    (net (code "237") (name "S_SDO") (class "Default")
      (node (ref "X-SOUTH") (pin "142") (pinfunction "142_142") (pintype "bidirectional"))
    )
    (net (code "238") (name "S_SPI_V") (class "Default")
      (node (ref "X-SOUTH") (pin "134") (pinfunction "134_134") (pintype "bidirectional"))
      (node (ref "X-SOUTH") (pin "136") (pinfunction "136_136") (pintype "bidirectional"))
    )
    (net (code "239") (name "S_VE") (class "Default")
      (node (ref "X-SOUTH") (pin "13") (pinfunction "13_13") (pintype "bidirectional"))
      (node (ref "X-SOUTH") (pin "19") (pinfunction "19_19") (pintype "bidirectional"))
      (node (ref "X-SOUTH") (pin "25") (pinfunction "25_25") (pintype "bidirectional"))
      (node (ref "X-SOUTH") (pin "31") (pinfunction "31_31") (pintype "bidirectional"))
      (node (ref "X-SOUTH") (pin "37") (pinfunction "37_37") (pintype "bidirectional"))
    )
    (net (code "240") (name "S_VE_CV") (class "Default")
      (node (ref "C11") (pin "1") (pinfunction "1_1") (pintype "passive"))
      (node (ref "R10") (pin "1") (pinfunction "1_1") (pintype "passive"))
      (node (ref "X-SOUTH") (pin "2") (pinfunction "2_2") (pintype "bidirectional"))
    )
    (net (code "241") (name "S_VE_OV") (class "Default")
      (node (ref "USE") (pin "7") (pinfunction "OUTB_7") (pintype "output"))
      (node (ref "X-SOUTH") (pin "1") (pinfunction "1_1") (pintype "bidirectional"))
    )
    (net (code "242") (name "S_VE_UV") (class "Default")
      (node (ref "USE") (pin "1") (pinfunction "OUTA_1") (pintype "output"))
      (node (ref "X-SOUTH") (pin "7") (pinfunction "7_7") (pintype "bidirectional"))
    )
    (net (code "243") (name "S_VS") (class "Default")
      (node (ref "C45") (pin "1") (pinfunction "1_1") (pintype "passive"))
      (node (ref "C46") (pin "1") (pinfunction "1_1") (pintype "passive"))
      (node (ref "C47") (pin "1") (pinfunction "1_1") (pintype "passive"))
      (node (ref "C48") (pin "1") (pinfunction "1_1") (pintype "passive"))
      (node (ref "C49") (pin "1") (pinfunction "1_1") (pintype "passive"))
      (node (ref "C72") (pin "1") (pinfunction "1_1") (pintype "passive"))
      (node (ref "C73") (pin "1") (pinfunction "1_1") (pintype "passive"))
      (node (ref "C74") (pin "1") (pinfunction "1_1") (pintype "passive"))
      (node (ref "C81") (pin "1") (pinfunction "1_1") (pintype "passive"))
      (node (ref "C82") (pin "1") (pinfunction "1_1") (pintype "passive"))
      (node (ref "C83") (pin "1") (pinfunction "1_1") (pintype "passive"))
      (node (ref "SENSOR") (pin "A30") (pinfunction "VDD_PIX_A30") (pintype "power_in"))
      (node (ref "SENSOR") (pin "D28") (pinfunction "VDD_PIX_D28") (pintype "power_in"))
      (node (ref "SENSOR") (pin "D30") (pinfunction "VDD_PIX_D30") (pintype "power_in"))
      (node (ref "SENSOR") (pin "G1") (pinfunction "VDD_PIX_G1") (pintype "power_in"))
      (node (ref "SENSOR") (pin "H28") (pinfunction "VDD_PIX_H28") (pintype "power_in"))
      (node (ref "TP6") (pin "TP") (pinfunction "TP_TP") (pintype "input"))
      (node (ref "X-SOUTH") (pin "49") (pinfunction "49_49") (pintype "bidirectional"))
      (node (ref "X-SOUTH") (pin "55") (pinfunction "55_55") (pintype "bidirectional"))
      (node (ref "X-SOUTH") (pin "61") (pinfunction "61_61") (pintype "bidirectional"))
      (node (ref "X-SOUTH") (pin "67") (pinfunction "67_67") (pintype "bidirectional"))
      (node (ref "X-SOUTH") (pin "73") (pinfunction "73_73") (pintype "bidirectional"))
      (node (ref "X-SOUTH") (pin "79") (pinfunction "79_79") (pintype "bidirectional"))
      (node (ref "X-SOUTH") (pin "85") (pinfunction "85_85") (pintype "bidirectional"))
      (node (ref "X-SOUTH") (pin "91") (pinfunction "91_91") (pintype "bidirectional"))
      (node (ref "X-SOUTH") (pin "97") (pinfunction "97_97") (pintype "bidirectional"))
    )
    (net (code "244") (name "S_VS_CV") (class "Default")
      (node (ref "C12") (pin "1") (pinfunction "1_1") (pintype "passive"))
      (node (ref "R13") (pin "1") (pinfunction "1_1") (pintype "passive"))
      (node (ref "X-SOUTH") (pin "4") (pinfunction "4_4") (pintype "bidirectional"))
    )
    (net (code "245") (name "S_VS_OV") (class "Default")
      (node (ref "USS") (pin "7") (pinfunction "OUTB_7") (pintype "output"))
      (node (ref "X-SOUTH") (pin "3") (pinfunction "3_3") (pintype "bidirectional"))
    )
    (net (code "246") (name "S_VS_UV") (class "Default")
      (node (ref "USS") (pin "1") (pinfunction "OUTA_1") (pintype "output"))
      (node (ref "X-SOUTH") (pin "9") (pinfunction "9_9") (pintype "bidirectional"))
    )
    (net (code "247") (name "S_VW") (class "Default")
      (node (ref "C90") (pin "1") (pinfunction "1_1") (pintype "passive"))
      (node (ref "U3") (pin "1") (pinfunction "BIAS_1") (pintype "power_in"))
      (node (ref "U3") (pin "3") (pinfunction "IN_3") (pintype "power_in"))
      (node (ref "X-SOUTH") (pin "109") (pinfunction "109_109") (pintype "bidirectional"))
      (node (ref "X-SOUTH") (pin "115") (pinfunction "115_115") (pintype "bidirectional"))
      (node (ref "X-SOUTH") (pin "121") (pinfunction "121_121") (pintype "bidirectional"))
      (node (ref "X-SOUTH") (pin "127") (pinfunction "127_127") (pintype "bidirectional"))
      (node (ref "X-SOUTH") (pin "133") (pinfunction "133_133") (pintype "bidirectional"))
    )
    (net (code "248") (name "S_VW_CV") (class "Default")
      (node (ref "C13") (pin "1") (pinfunction "1_1") (pintype "passive"))
      (node (ref "R16") (pin "1") (pinfunction "1_1") (pintype "passive"))
      (node (ref "X-SOUTH") (pin "6") (pinfunction "6_6") (pintype "bidirectional"))
    )
    (net (code "249") (name "S_VW_OV") (class "Default")
      (node (ref "USW") (pin "7") (pinfunction "OUTB_7") (pintype "output"))
      (node (ref "X-SOUTH") (pin "5") (pinfunction "5_5") (pintype "bidirectional"))
    )
    (net (code "250") (name "S_VW_UV") (class "Default")
      (node (ref "USW") (pin "1") (pinfunction "OUTA_1") (pintype "output"))
      (node (ref "X-SOUTH") (pin "11") (pinfunction "11_11") (pintype "bidirectional"))
    )
    (net (code "251") (name "TDIG1") (class "Default")
      (node (ref "SENSOR") (pin "G27") (pinfunction "TDIG1_G27") (pintype "output"))
      (node (ref "U5") (pin "9") (pinfunction "B4_9") (pintype "bidirectional"))
    )
    (net (code "252") (name "TDIG2") (class "Default")
      (node (ref "SENSOR") (pin "G26") (pinfunction "TDIG2_G26") (pintype "output"))
      (node (ref "U6") (pin "11") (pinfunction "B2_11") (pintype "bidirectional"))
    )
    (net (code "253") (name "T_EXP1") (class "Default")
      (node (ref "SENSOR") (pin "H30") (pinfunction "T_EXP1_H30") (pintype "input"))
      (node (ref "U5") (pin "12") (pinfunction "B1_12") (pintype "bidirectional"))
    )
    (net (code "254") (name "T_EXP2") (class "Default")
      (node (ref "SENSOR") (pin "E29") (pinfunction "T_EXP2_E29") (pintype "input"))
      (node (ref "U6") (pin "10") (pinfunction "B3_10") (pintype "bidirectional"))
    )
    (net (code "255") (name "VRAMP1") (class "Default")
      (node (ref "C16") (pin "1") (pinfunction "1_1") (pintype "passive"))
      (node (ref "R23") (pin "1") (pinfunction "1_1") (pintype "passive"))
      (node (ref "SENSOR") (pin "G29") (pinfunction "VRAMP1_G29") (pintype "bidirectional"))
    )
    (net (code "256") (name "VRAMP2") (class "Default")
      (node (ref "C17") (pin "1") (pinfunction "1_1") (pintype "passive"))
      (node (ref "R23") (pin "2") (pinfunction "2_2") (pintype "passive"))
      (node (ref "SENSOR") (pin "F29") (pinfunction "VRAMP2_F29") (pintype "bidirectional"))
    )
    (net (code "257") (name "VTREF") (class "Default")
      (node (ref "C65") (pin "1") (pinfunction "1_1") (pintype "passive"))
      (node (ref "C91") (pin "2") (pinfunction "2_2") (pintype "passive"))
      (node (ref "R21") (pin "2") (pinfunction "2_2") (pintype "passive"))
      (node (ref "R24") (pin "1") (pinfunction "1_1") (pintype "passive"))
      (node (ref "SENSOR") (pin "B2") (pinfunction "VTREF_B2") (pintype "bidirectional"))
      (node (ref "U3") (pin "4") (pinfunction "OUT_4") (pintype "power_in"))
    )
    (net (code "258") (name "VTSIG") (class "Default")
      (node (ref "C66") (pin "1") (pinfunction "1_1") (pintype "passive"))
      (node (ref "R24") (pin "2") (pinfunction "2_2") (pintype "passive"))
      (node (ref "SENSOR") (pin "C2") (pinfunction "VTSIG_C2") (pintype "bidirectional"))
    )
    (net (code "259") (name "unconnected-(U1-NC-Pad2)") (class "Default")
      (node (ref "U1") (pin "2") (pinfunction "NC_2") (pintype "no_connect"))
    )
    (net (code "260") (name "unconnected-(U1-NC-Pad4)") (class "Default")
      (node (ref "U1") (pin "4") (pinfunction "NC_4") (pintype "no_connect"))
    )
    (net (code "261") (name "unconnected-(U1-NC-Pad5)") (class "Default")
      (node (ref "U1") (pin "5") (pinfunction "NC_5") (pintype "no_connect"))
    )
    (net (code "262") (name "unconnected-(U2-NC-Pad2)") (class "Default")
      (node (ref "U2") (pin "2") (pinfunction "NC_2") (pintype "no_connect"))
    )
    (net (code "263") (name "unconnected-(U2-NC-Pad4)") (class "Default")
      (node (ref "U2") (pin "4") (pinfunction "NC_4") (pintype "no_connect"))
    )
    (net (code "264") (name "unconnected-(U2-NC-Pad5)") (class "Default")
      (node (ref "U2") (pin "5") (pinfunction "NC_5") (pintype "no_connect"))
    )
    (net (code "265") (name "unconnected-(U4-2B2-Pad12)") (class "Default")
      (node (ref "U4") (pin "12") (pinfunction "2B2_12") (pintype "output"))
    )
    (net (code "266") (name "unconnected-(U7-OS-Pad3)") (class "Default")
      (node (ref "U7") (pin "3") (pinfunction "OS_3") (pintype "output"))
    )
    (net (code "267") (name "unconnected-(X-NORTH-PadM1)") (class "Default")
      (node (ref "X-NORTH") (pin "M1") (pinfunction "M1_M1") (pintype "bidirectional"))
    )
    (net (code "268") (name "unconnected-(X-NORTH-PadM2)") (class "Default")
      (node (ref "X-NORTH") (pin "M2") (pinfunction "M2_M2") (pintype "bidirectional"))
    )
    (net (code "269") (name "unconnected-(X-SOUTH-PadM1)") (class "Default")
      (node (ref "X-SOUTH") (pin "M1") (pinfunction "M1_M1") (pintype "bidirectional"))
    )
    (net (code "270") (name "unconnected-(X-SOUTH-PadM2)") (class "Default")
      (node (ref "X-SOUTH") (pin "M2") (pinfunction "M2_M2") (pintype "bidirectional"))
    )
  )
)
